# Sheet2.net
KiCad netlist of a schematic drawn in Altium Designer
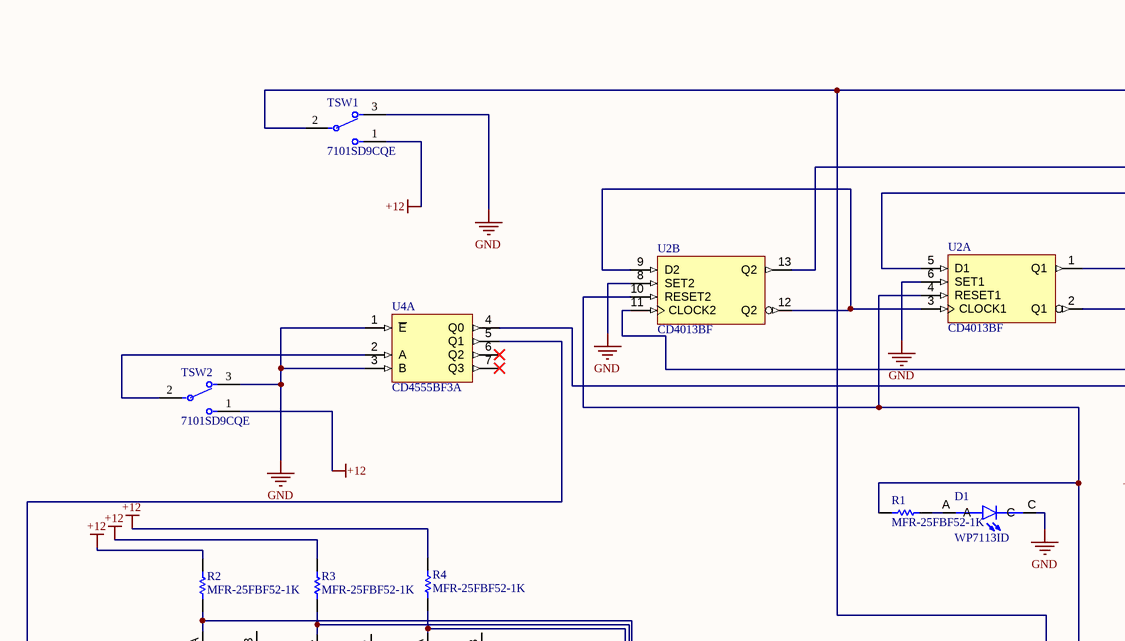
[diagram p0: Sheet2.SchDoc, centre column 2 of 4]
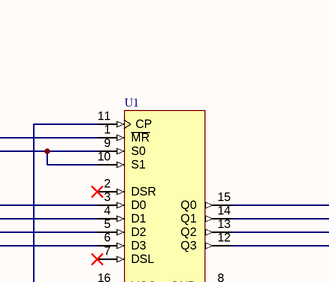
[diagram p1: Sheet2.SchDoc, centre column 3 of 4]
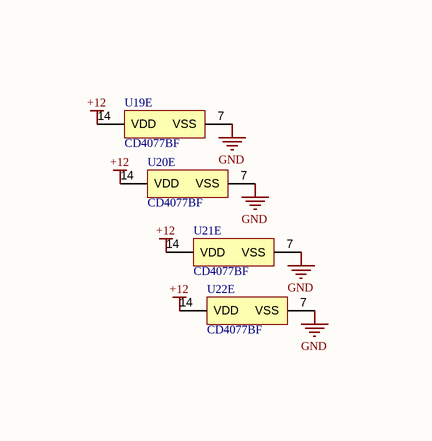
[diagram p2: Sheet2.SchDoc, centre column 4 of 4]
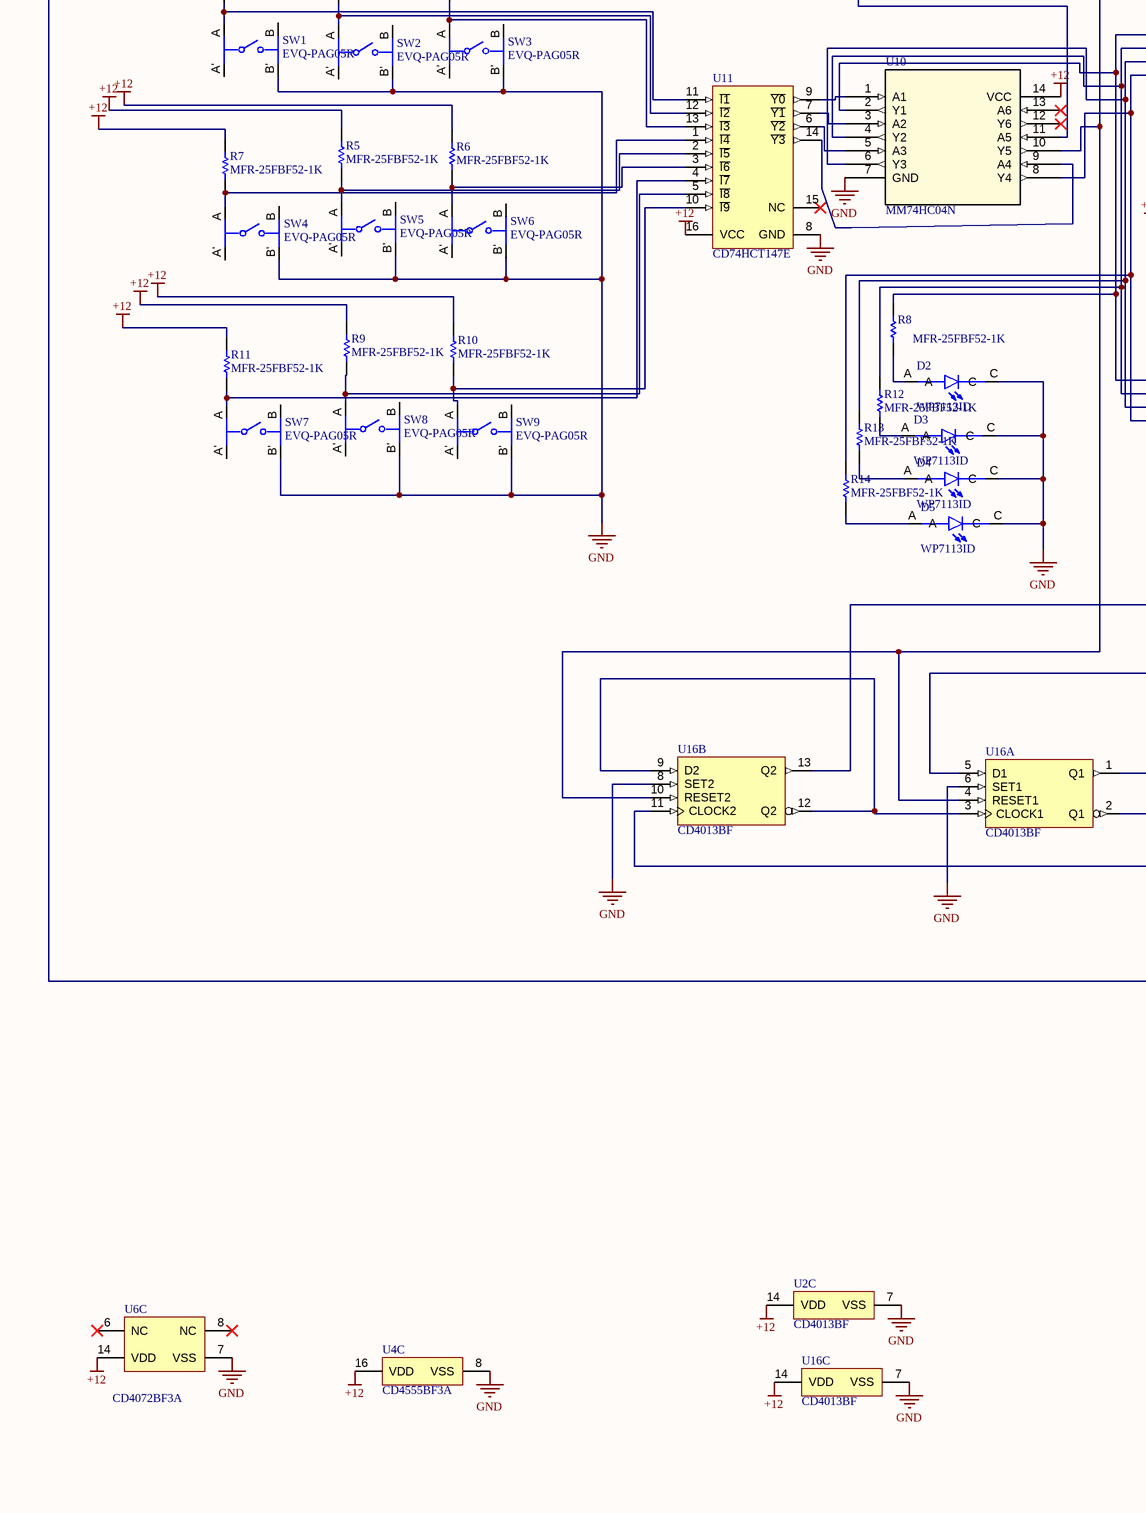
[diagram p3: Sheet2.SchDoc, bottom column 2 of 4]
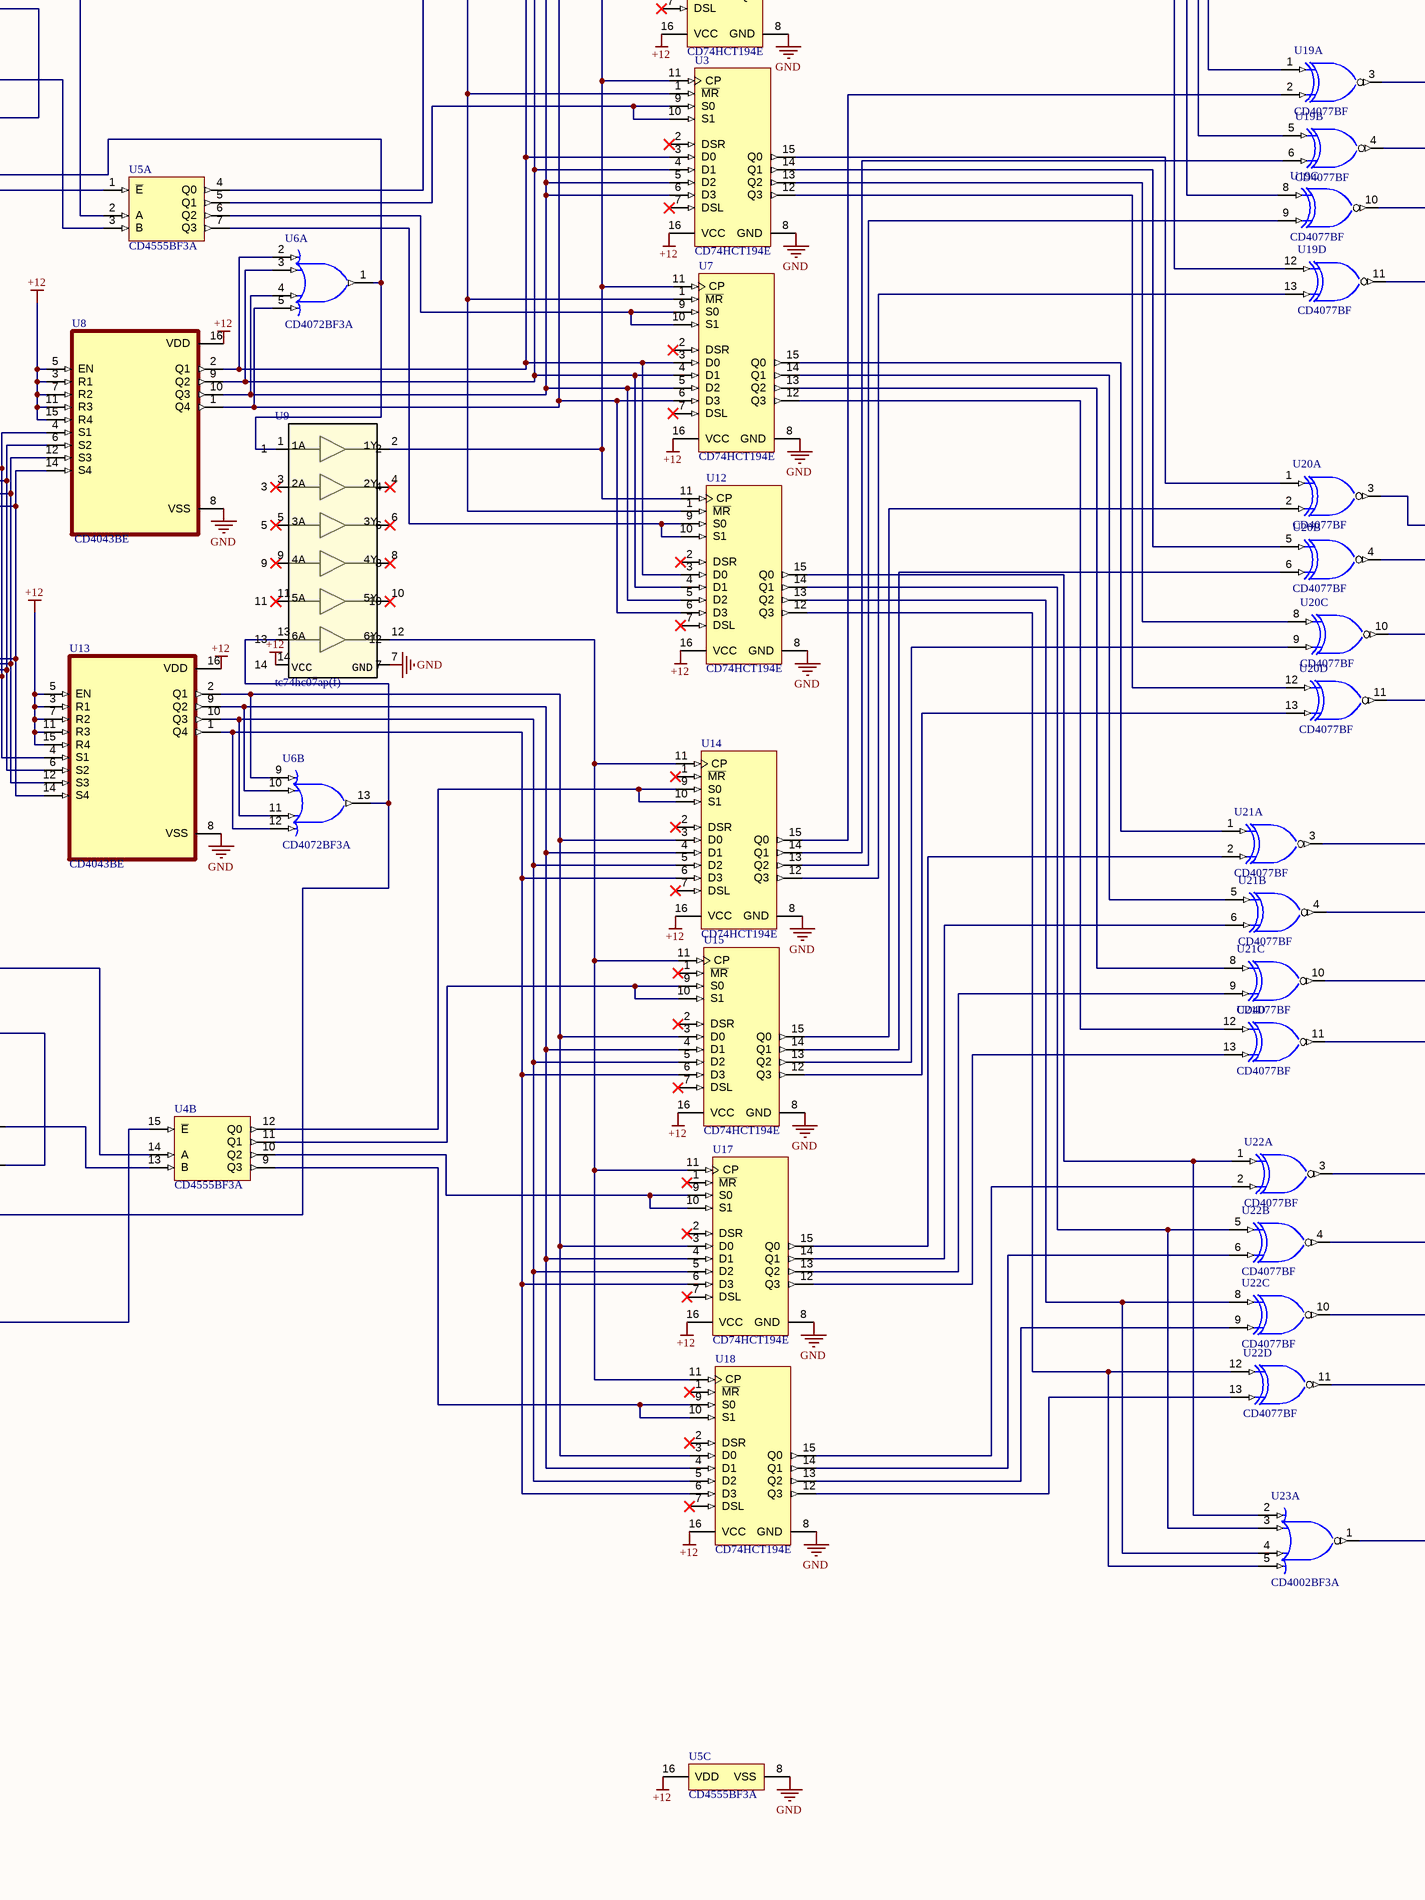
[diagram p4: Sheet2.SchDoc, bottom column 3 of 4]
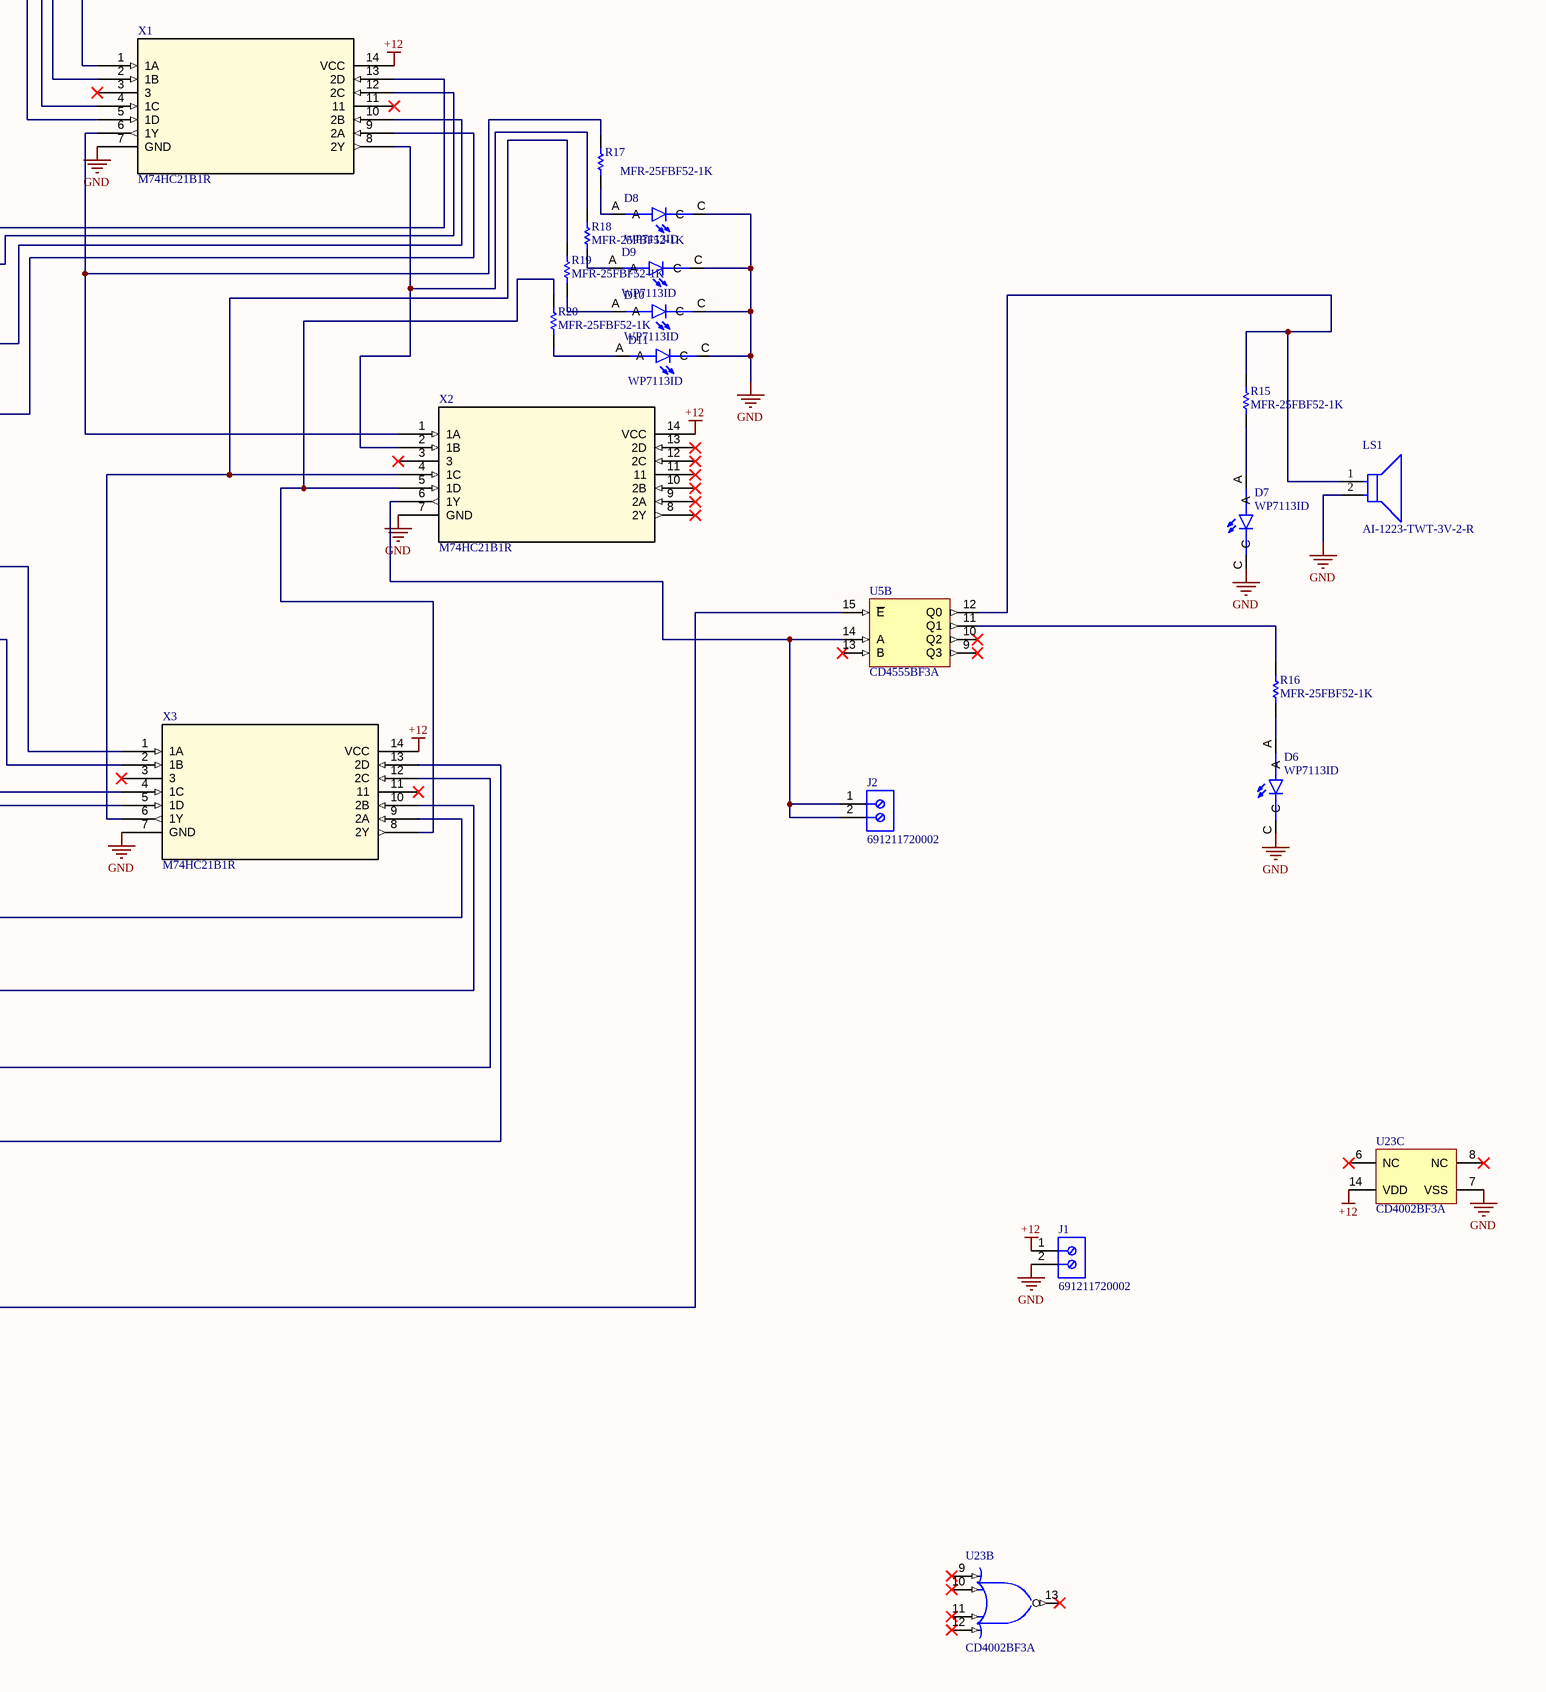
[diagram p5: Sheet2.SchDoc, bottom column 4 of 4]

(export (version "E")
  (design (tool "Eeschema 10.0.6"))
  (components
    (comp (ref "D1")
      (value "WP7113ID")
      (footprint "LED_WP7113ID")
      (description "Red 617nm LED Indication - Discrete 2V Radial")
      (fields (field (name "MF") "Kingbright"))
      (libsource (lib "WP7113ID (1)") (part "WP7113ID"))
    )
    (comp (ref "D2")
      (value "WP7113ID")
      (footprint "LED_WP7113ID")
      (description "Red 617nm LED Indication - Discrete 2V Radial")
      (fields (field (name "MF") "Kingbright"))
      (libsource (lib "WP7113ID") (part "WP7113ID"))
    )
    (comp (ref "D3")
      (value "WP7113ID")
      (footprint "LED_WP7113ID")
      (description "Red 617nm LED Indication - Discrete 2V Radial")
      (fields (field (name "MF") "Kingbright"))
      (libsource (lib "WP7113ID") (part "WP7113ID"))
    )
    (comp (ref "D4")
      (value "WP7113ID")
      (footprint "LED_WP7113ID")
      (description "Red 617nm LED Indication - Discrete 2V Radial")
      (fields (field (name "MF") "Kingbright"))
      (libsource (lib "WP7113ID") (part "WP7113ID"))
    )
    (comp (ref "D5")
      (value "WP7113ID")
      (footprint "LED_WP7113ID")
      (description "Red 617nm LED Indication - Discrete 2V Radial")
      (fields (field (name "MF") "Kingbright"))
      (libsource (lib "WP7113ID") (part "WP7113ID"))
    )
    (comp (ref "D6")
      (value "WP7113ID")
      (footprint "LED_WP7113ID")
      (description "Red 617nm LED Indication - Discrete 2V Radial")
      (fields (field (name "MF") "Kingbright"))
      (libsource (lib "WP7113ID (1)") (part "WP7113ID"))
    )
    (comp (ref "D7")
      (value "WP7113ID")
      (footprint "LED_WP7113ID")
      (description "Red 617nm LED Indication - Discrete 2V Radial")
      (fields (field (name "MF") "Kingbright"))
      (libsource (lib "WP7113ID (1)") (part "WP7113ID"))
    )
    (comp (ref "D8")
      (value "WP7113ID")
      (footprint "LED_WP7113ID")
      (description "Red 617nm LED Indication - Discrete 2V Radial")
      (fields (field (name "MF") "Kingbright"))
      (libsource (lib "WP7113ID") (part "WP7113ID"))
    )
    (comp (ref "D9")
      (value "WP7113ID")
      (footprint "LED_WP7113ID")
      (description "Red 617nm LED Indication - Discrete 2V Radial")
      (fields (field (name "MF") "Kingbright"))
      (libsource (lib "WP7113ID") (part "WP7113ID"))
    )
    (comp (ref "D10")
      (value "WP7113ID")
      (footprint "LED_WP7113ID")
      (description "Red 617nm LED Indication - Discrete 2V Radial")
      (fields (field (name "MF") "Kingbright"))
      (libsource (lib "WP7113ID") (part "WP7113ID"))
    )
    (comp (ref "D11")
      (value "WP7113ID")
      (footprint "LED_WP7113ID")
      (description "Red 617nm LED Indication - Discrete 2V Radial")
      (fields (field (name "MF") "Kingbright"))
      (libsource (lib "WP7113ID") (part "WP7113ID"))
    )
    (comp (ref "J1")
      (value "691211720002")
      (footprint "691211720002")
      (description "211 Series 5MM Pitch Straight, Pcb Terminal Block, Through Hole, 2 Way")
      (fields (field (name "VOLTAGE") "300V"))
      (libsource (lib "Altium Content Vault") (part "TBL - 1R - 02P - Screw"))
    )
    (comp (ref "J2")
      (value "691211720002")
      (footprint "691211720002")
      (description "211 Series 5MM Pitch Straight, Pcb Terminal Block, Through Hole, 2 Way")
      (fields (field (name "VOLTAGE") "300V"))
      (libsource (lib "Altium Content Vault") (part "TBL - 1R - 02P - Screw"))
    )
    (comp (ref "LS1")
      (value "AI-1223-TWT-3V-2-R")
      (footprint "FP-AI-1223-TWT-3V-2-R-MFG")
      (description "BUZZER MAGNETIC 3V 12MM TH")
      (libsource (lib "Altium Content Vault") (part "1973c4b650225fd2ddacaff6b763965"))
    )
    (comp (ref "R1")
      (value "MFR-25FBF52-1K")
      (footprint "RESA60-630X240")
      (description "Axial Resistor, 1 KOhm, +/- 1%, 250 mW, -55 to 155 degC, 2-Pin THD, RoHS, Bulk")
      (fields (field (name "TOLERANCE") "1%"))
      (libsource (lib "Altium Content Vault") (part "RES-2"))
    )
    (comp (ref "R2")
      (value "MFR-25FBF52-1K")
      (footprint "RESA60-630X240")
      (description "Axial Resistor, 1 KOhm, +/- 1%, 250 mW, -55 to 155 degC, 2-Pin THD, RoHS, Bulk")
      (fields (field (name "TOLERANCE") "1%"))
      (libsource (lib "Altium Content Vault") (part "RES-2"))
    )
    (comp (ref "R3")
      (value "MFR-25FBF52-1K")
      (footprint "RESA60-630X240")
      (description "Axial Resistor, 1 KOhm, +/- 1%, 250 mW, -55 to 155 degC, 2-Pin THD, RoHS, Bulk")
      (fields (field (name "TOLERANCE") "1%"))
      (libsource (lib "Altium Content Vault") (part "RES-2"))
    )
    (comp (ref "R4")
      (value "MFR-25FBF52-1K")
      (footprint "RESA60-630X240")
      (description "Axial Resistor, 1 KOhm, +/- 1%, 250 mW, -55 to 155 degC, 2-Pin THD, RoHS, Bulk")
      (fields (field (name "TOLERANCE") "1%"))
      (libsource (lib "Altium Content Vault") (part "RES-2"))
    )
    (comp (ref "R5")
      (value "MFR-25FBF52-1K")
      (footprint "RESA60-630X240")
      (description "Axial Resistor, 1 KOhm, +/- 1%, 250 mW, -55 to 155 degC, 2-Pin THD, RoHS, Bulk")
      (fields (field (name "TOLERANCE") "1%"))
      (libsource (lib "Altium Content Vault") (part "RES-2"))
    )
    (comp (ref "R6")
      (value "MFR-25FBF52-1K")
      (footprint "RESA60-630X240")
      (description "Axial Resistor, 1 KOhm, +/- 1%, 250 mW, -55 to 155 degC, 2-Pin THD, RoHS, Bulk")
      (fields (field (name "TOLERANCE") "1%"))
      (libsource (lib "Altium Content Vault") (part "RES-2"))
    )
    (comp (ref "R7")
      (value "MFR-25FBF52-1K")
      (footprint "RESA60-630X240")
      (description "Axial Resistor, 1 KOhm, +/- 1%, 250 mW, -55 to 155 degC, 2-Pin THD, RoHS, Bulk")
      (fields (field (name "TOLERANCE") "1%"))
      (libsource (lib "Altium Content Vault") (part "RES-2"))
    )
    (comp (ref "R8")
      (value "MFR-25FBF52-1K")
      (footprint "RESA60-630X240")
      (description "Axial Resistor, 1 KOhm, +/- 1%, 250 mW, -55 to 155 degC, 2-Pin THD, RoHS, Bulk")
      (fields (field (name "TOLERANCE") "1%"))
      (libsource (lib "Altium Content Vault") (part "RES-2"))
    )
    (comp (ref "R9")
      (value "MFR-25FBF52-1K")
      (footprint "RESA60-630X240")
      (description "Axial Resistor, 1 KOhm, +/- 1%, 250 mW, -55 to 155 degC, 2-Pin THD, RoHS, Bulk")
      (fields (field (name "TOLERANCE") "1%"))
      (libsource (lib "Altium Content Vault") (part "RES-2"))
    )
    (comp (ref "R10")
      (value "MFR-25FBF52-1K")
      (footprint "RESA60-630X240")
      (description "Axial Resistor, 1 KOhm, +/- 1%, 250 mW, -55 to 155 degC, 2-Pin THD, RoHS, Bulk")
      (fields (field (name "TOLERANCE") "1%"))
      (libsource (lib "Altium Content Vault") (part "RES-2"))
    )
    (comp (ref "R11")
      (value "MFR-25FBF52-1K")
      (footprint "RESA60-630X240")
      (description "Axial Resistor, 1 KOhm, +/- 1%, 250 mW, -55 to 155 degC, 2-Pin THD, RoHS, Bulk")
      (fields (field (name "TOLERANCE") "1%"))
      (libsource (lib "Altium Content Vault") (part "RES-2"))
    )
    (comp (ref "R12")
      (value "MFR-25FBF52-1K")
      (footprint "RESA60-630X240")
      (description "Axial Resistor, 1 KOhm, +/- 1%, 250 mW, -55 to 155 degC, 2-Pin THD, RoHS, Bulk")
      (fields (field (name "TOLERANCE") "1%"))
      (libsource (lib "Altium Content Vault") (part "RES-2"))
    )
    (comp (ref "R13")
      (value "MFR-25FBF52-1K")
      (footprint "RESA60-630X240")
      (description "Axial Resistor, 1 KOhm, +/- 1%, 250 mW, -55 to 155 degC, 2-Pin THD, RoHS, Bulk")
      (fields (field (name "TOLERANCE") "1%"))
      (libsource (lib "Altium Content Vault") (part "RES-2"))
    )
    (comp (ref "R14")
      (value "MFR-25FBF52-1K")
      (footprint "RESA60-630X240")
      (description "Axial Resistor, 1 KOhm, +/- 1%, 250 mW, -55 to 155 degC, 2-Pin THD, RoHS, Bulk")
      (fields (field (name "TOLERANCE") "1%"))
      (libsource (lib "Altium Content Vault") (part "RES-2"))
    )
    (comp (ref "R15")
      (value "MFR-25FBF52-1K")
      (footprint "RESA60-630X240")
      (description "Axial Resistor, 1 KOhm, +/- 1%, 250 mW, -55 to 155 degC, 2-Pin THD, RoHS, Bulk")
      (fields (field (name "TOLERANCE") "1%"))
      (libsource (lib "Altium Content Vault") (part "RES-2"))
    )
    (comp (ref "R16")
      (value "MFR-25FBF52-1K")
      (footprint "RESA60-630X240")
      (description "Axial Resistor, 1 KOhm, +/- 1%, 250 mW, -55 to 155 degC, 2-Pin THD, RoHS, Bulk")
      (fields (field (name "TOLERANCE") "1%"))
      (libsource (lib "Altium Content Vault") (part "RES-2"))
    )
    (comp (ref "R17")
      (value "MFR-25FBF52-1K")
      (footprint "RESA60-630X240")
      (description "Axial Resistor, 1 KOhm, +/- 1%, 250 mW, -55 to 155 degC, 2-Pin THD, RoHS, Bulk")
      (fields (field (name "TOLERANCE") "1%"))
      (libsource (lib "Altium Content Vault") (part "RES-2"))
    )
    (comp (ref "R18")
      (value "MFR-25FBF52-1K")
      (footprint "RESA60-630X240")
      (description "Axial Resistor, 1 KOhm, +/- 1%, 250 mW, -55 to 155 degC, 2-Pin THD, RoHS, Bulk")
      (fields (field (name "TOLERANCE") "1%"))
      (libsource (lib "Altium Content Vault") (part "RES-2"))
    )
    (comp (ref "R19")
      (value "MFR-25FBF52-1K")
      (footprint "RESA60-630X240")
      (description "Axial Resistor, 1 KOhm, +/- 1%, 250 mW, -55 to 155 degC, 2-Pin THD, RoHS, Bulk")
      (fields (field (name "TOLERANCE") "1%"))
      (libsource (lib "Altium Content Vault") (part "RES-2"))
    )
    (comp (ref "R20")
      (value "MFR-25FBF52-1K")
      (footprint "RESA60-630X240")
      (description "Axial Resistor, 1 KOhm, +/- 1%, 250 mW, -55 to 155 degC, 2-Pin THD, RoHS, Bulk")
      (fields (field (name "TOLERANCE") "1%"))
      (libsource (lib "Altium Content Vault") (part "RES-2"))
    )
    (comp (ref "SW1")
      (value "EVQ-PAG05R")
      (footprint "FP-EVQ-PAG05R-MFG")
      (description "SWITCH TACTILE SPST-NO 0.02A 15V")
      (libsource (lib "Altium Content Vault") (part "841f23923f71b23f3ea0ab5dfb78dcc"))
    )
    (comp (ref "SW2")
      (value "EVQ-PAG05R")
      (footprint "FP-EVQ-PAG05R-MFG")
      (description "SWITCH TACTILE SPST-NO 0.02A 15V")
      (libsource (lib "Altium Content Vault") (part "841f23923f71b23f3ea0ab5dfb78dcc"))
    )
    (comp (ref "SW3")
      (value "EVQ-PAG05R")
      (footprint "FP-EVQ-PAG05R-MFG")
      (description "SWITCH TACTILE SPST-NO 0.02A 15V")
      (libsource (lib "Altium Content Vault") (part "841f23923f71b23f3ea0ab5dfb78dcc"))
    )
    (comp (ref "SW4")
      (value "EVQ-PAG05R")
      (footprint "FP-EVQ-PAG05R-MFG")
      (description "SWITCH TACTILE SPST-NO 0.02A 15V")
      (libsource (lib "Altium Content Vault") (part "841f23923f71b23f3ea0ab5dfb78dcc"))
    )
    (comp (ref "SW5")
      (value "EVQ-PAG05R")
      (footprint "FP-EVQ-PAG05R-MFG")
      (description "SWITCH TACTILE SPST-NO 0.02A 15V")
      (libsource (lib "Altium Content Vault") (part "841f23923f71b23f3ea0ab5dfb78dcc"))
    )
    (comp (ref "SW6")
      (value "EVQ-PAG05R")
      (footprint "FP-EVQ-PAG05R-MFG")
      (description "SWITCH TACTILE SPST-NO 0.02A 15V")
      (libsource (lib "Altium Content Vault") (part "841f23923f71b23f3ea0ab5dfb78dcc"))
    )
    (comp (ref "SW7")
      (value "EVQ-PAG05R")
      (footprint "FP-EVQ-PAG05R-MFG")
      (description "SWITCH TACTILE SPST-NO 0.02A 15V")
      (libsource (lib "Altium Content Vault") (part "841f23923f71b23f3ea0ab5dfb78dcc"))
    )
    (comp (ref "SW8")
      (value "EVQ-PAG05R")
      (footprint "FP-EVQ-PAG05R-MFG")
      (description "SWITCH TACTILE SPST-NO 0.02A 15V")
      (libsource (lib "Altium Content Vault") (part "841f23923f71b23f3ea0ab5dfb78dcc"))
    )
    (comp (ref "SW9")
      (value "EVQ-PAG05R")
      (footprint "FP-EVQ-PAG05R-MFG")
      (description "SWITCH TACTILE SPST-NO 0.02A 15V")
      (libsource (lib "Altium Content Vault") (part "841f23923f71b23f3ea0ab5dfb78dcc"))
    )
    (comp (ref "TSW1")
      (value "7101SD9CQE")
      (footprint "FP-7101SD9CQE-MFG")
      (libsource (lib "Altium Content Vault") (part "27fba41b97997be56c5a5b5d23f1c5a"))
    )
    (comp (ref "TSW2")
      (value "7101SD9CQE")
      (footprint "FP-7101SD9CQE-MFG")
      (libsource (lib "Altium Content Vault") (part "27fba41b97997be56c5a5b5d23f1c5a"))
    )
    (comp (ref "U1")
      (value "CD74HCT194E")
      (footprint "N0016A")
      (description "High Speed CMOS Logic 4-Bit Bidirectional Universal Shift Register, N0016A, TUBE")
      (fields
        (field (name "GENERIC PART NUMBER") "CD74HCT194")
        (field (name "MANUFACTURER") "Texas Instruments")
      )
      (libsource (lib "Altium Content Vault") (part "TI-CD74HCX194-16"))
    )
    (comp (ref "U2")
      (value "CD4013BF")
      (footprint "J0014A")
      (description "CMOS Dual D-Type Flip Flop, J0014A, TUBE")
      (fields
        (field (name "GENERIC PART NUMBER") "CD4013B-MIL")
        (field (name "MANUFACTURER") "Texas Instruments")
      )
      (libsource (lib "Altium Content Vault") (part "TI-CD4013B-14"))
    )
    (comp (ref "U3")
      (value "CD74HCT194E")
      (footprint "N0016A")
      (description "High Speed CMOS Logic 4-Bit Bidirectional Universal Shift Register, N0016A, TUBE")
      (fields
        (field (name "GENERIC PART NUMBER") "CD74HCT194")
        (field (name "MANUFACTURER") "Texas Instruments")
      )
      (libsource (lib "Altium Content Vault") (part "TI-CD74HCX194-16"))
    )
    (comp (ref "U4")
      (value "CD4555BF3A")
      (footprint "J0016A")
      (description "CMOS Dual Binary to 1-of-4 Decoder/Demultiplexer with Outputs High on Select, J0016A, TUBE")
      (fields
        (field (name "MANUFACTURER") "Texas Instruments")
        (field (name "GENERIC PART NUMBER") "CD4555B-MIL")
      )
      (libsource (lib "Altium Content Vault") (part "TI-CD4555B-16"))
    )
    (comp (ref "U5")
      (value "CD4555BF3A")
      (footprint "J0016A")
      (description "CMOS Dual Binary to 1-of-4 Decoder/Demultiplexer with Outputs High on Select, J0016A, TUBE")
      (fields
        (field (name "MANUFACTURER") "Texas Instruments")
        (field (name "GENERIC PART NUMBER") "CD4555B-MIL")
      )
      (libsource (lib "Altium Content Vault") (part "TI-CD4555B-16"))
    )
    (comp (ref "U6")
      (value "CD4072BF3A")
      (footprint "J0014A")
      (description "CMOS Dual 4-Input OR Gate, J0014A, TUBE")
      (fields
        (field (name "GENERIC PART NUMBER") "CD4072B-MIL")
        (field (name "MANUFACTURER") "Texas Instruments")
      )
      (libsource (lib "Altium Content Vault") (part "TI-CD4072B-14"))
    )
    (comp (ref "U7")
      (value "CD74HCT194E")
      (footprint "N0016A")
      (description "High Speed CMOS Logic 4-Bit Bidirectional Universal Shift Register, N0016A, TUBE")
      (fields
        (field (name "GENERIC PART NUMBER") "CD74HCT194")
        (field (name "MANUFACTURER") "Texas Instruments")
      )
      (libsource (lib "Altium Content Vault") (part "TI-CD74HCX194-16"))
    )
    (comp (ref "U8")
      (value "CD4043BE")
      (footprint "DIP794W45P254L1969H508Q16")
      (description "CMOS Quad NOR R/S Latch with 3-State Outputs")
      (fields (field (name "MF") "Texas Instruments"))
      (libsource (lib "CD4043BE") (part "CD4043BE"))
    )
    (comp (ref "U9")
      (value "tc74hc07ap(f)")
      (footprint "DIP14_TOS")
      (description "Hex Buffer, DIP14")
      (fields (field (name "COPYRIGHT") "Copyright (C) 2025 Ultra Librarian. All rights reserved."))
      (libsource (lib "tc74hc07apf") (part "tc74hc07apf"))
    )
    (comp (ref "U10")
      (value "MM74HC04N")
      (footprint "PDIP14_19P56X6P35_ONS")
      (description "Description")
      (fields (field (name "COPYRIGHT") "Copyright (C) 2026 Ultra Librarian. All rights reserved."))
      (libsource (lib "MM74HC04N") (part "MM74HC04N"))
    )
    (comp (ref "U11")
      (value "CD74HCT147E")
      (footprint "N0016A")
      (description "High Speed CMOS Logic 10-to-4 Line Priority Encoder, N0016A, TUBE")
      (fields
        (field (name "MANUFACTURER") "Texas Instruments")
        (field (name "GENERIC PART NUMBER") "CD74HCT147")
      )
      (libsource (lib "Altium Content Vault") (part "TI-CDX4HCX147-16"))
    )
    (comp (ref "U12")
      (value "CD74HCT194E")
      (footprint "N0016A")
      (description "High Speed CMOS Logic 4-Bit Bidirectional Universal Shift Register, N0016A, TUBE")
      (fields
        (field (name "GENERIC PART NUMBER") "CD74HCT194")
        (field (name "MANUFACTURER") "Texas Instruments")
      )
      (libsource (lib "Altium Content Vault") (part "TI-CD74HCX194-16"))
    )
    (comp (ref "U13")
      (value "CD4043BE")
      (footprint "DIP794W45P254L1969H508Q16")
      (description "CMOS Quad NOR R/S Latch with 3-State Outputs")
      (fields (field (name "MF") "Texas Instruments"))
      (libsource (lib "CD4043BE") (part "CD4043BE"))
    )
    (comp (ref "U14")
      (value "CD74HCT194E")
      (footprint "N0016A")
      (description "High Speed CMOS Logic 4-Bit Bidirectional Universal Shift Register, N0016A, TUBE")
      (fields
        (field (name "GENERIC PART NUMBER") "CD74HCT194")
        (field (name "MANUFACTURER") "Texas Instruments")
      )
      (libsource (lib "Altium Content Vault") (part "TI-CD74HCX194-16"))
    )
    (comp (ref "U15")
      (value "CD74HCT194E")
      (footprint "N0016A")
      (description "High Speed CMOS Logic 4-Bit Bidirectional Universal Shift Register, N0016A, TUBE")
      (fields
        (field (name "GENERIC PART NUMBER") "CD74HCT194")
        (field (name "MANUFACTURER") "Texas Instruments")
      )
      (libsource (lib "Altium Content Vault") (part "TI-CD74HCX194-16"))
    )
    (comp (ref "U16")
      (value "CD4013BF")
      (footprint "J0014A")
      (description "CMOS Dual D-Type Flip Flop, J0014A, TUBE")
      (fields
        (field (name "GENERIC PART NUMBER") "CD4013B-MIL")
        (field (name "MANUFACTURER") "Texas Instruments")
      )
      (libsource (lib "Altium Content Vault") (part "TI-CD4013B-14"))
    )
    (comp (ref "U17")
      (value "CD74HCT194E")
      (footprint "N0016A")
      (description "High Speed CMOS Logic 4-Bit Bidirectional Universal Shift Register, N0016A, TUBE")
      (fields
        (field (name "GENERIC PART NUMBER") "CD74HCT194")
        (field (name "MANUFACTURER") "Texas Instruments")
      )
      (libsource (lib "Altium Content Vault") (part "TI-CD74HCX194-16"))
    )
    (comp (ref "U18")
      (value "CD74HCT194E")
      (footprint "N0016A")
      (description "High Speed CMOS Logic 4-Bit Bidirectional Universal Shift Register, N0016A, TUBE")
      (fields
        (field (name "GENERIC PART NUMBER") "CD74HCT194")
        (field (name "MANUFACTURER") "Texas Instruments")
      )
      (libsource (lib "Altium Content Vault") (part "TI-CD74HCX194-16"))
    )
    (comp (ref "U19")
      (value "CD4077BF")
      (footprint "J0014A")
      (description "CMOS Quad Exclusive-NOR Gate, J0014A, TUBE")
      (fields
        (field (name "MANUFACTURER") "Texas Instruments")
        (field (name "GENERIC PART NUMBER") "CD4077B-MIL")
      )
      (libsource (lib "Altium Content Vault") (part "TI-XNOR-4-2IN-14"))
    )
    (comp (ref "U20")
      (value "CD4077BF")
      (footprint "J0014A")
      (description "CMOS Quad Exclusive-NOR Gate, J0014A, TUBE")
      (fields
        (field (name "MANUFACTURER") "Texas Instruments")
        (field (name "GENERIC PART NUMBER") "CD4077B-MIL")
      )
      (libsource (lib "Altium Content Vault") (part "TI-XNOR-4-2IN-14"))
    )
    (comp (ref "U21")
      (value "CD4077BF")
      (footprint "J0014A")
      (description "CMOS Quad Exclusive-NOR Gate, J0014A, TUBE")
      (fields
        (field (name "MANUFACTURER") "Texas Instruments")
        (field (name "GENERIC PART NUMBER") "CD4077B-MIL")
      )
      (libsource (lib "Altium Content Vault") (part "TI-XNOR-4-2IN-14"))
    )
    (comp (ref "U22")
      (value "CD4077BF")
      (footprint "J0014A")
      (description "CMOS Quad Exclusive-NOR Gate, J0014A, TUBE")
      (fields
        (field (name "MANUFACTURER") "Texas Instruments")
        (field (name "GENERIC PART NUMBER") "CD4077B-MIL")
      )
      (libsource (lib "Altium Content Vault") (part "TI-XNOR-4-2IN-14"))
    )
    (comp (ref "U23")
      (value "CD4002BF3A")
      (footprint "J0014A")
      (description "CMOS Dual 4-Input NOR Gate, J0014A, TUBE")
      (fields
        (field (name "MANUFACTURER") "Texas Instruments")
        (field (name "GENERIC PART NUMBER") "CD4002B-MIL")
      )
      (libsource (lib "Altium Content Vault") (part "TI-CD4002B-MIL-J0014A-14"))
    )
    (comp (ref "X1")
      (value "M74HC21B1R")
      (footprint "DIP14_300_STH")
      (description "No Description Available")
      (fields (field (name "COPYRIGHT") "Copyright (C) 2026 Ultra Librarian. All rights reserved."))
      (libsource (lib "M74HC21B1R") (part "M74HC21B1R"))
    )
    (comp (ref "X2")
      (value "M74HC21B1R")
      (footprint "DIP14_300_STH")
      (description "No Description Available")
      (fields (field (name "COPYRIGHT") "Copyright (C) 2026 Ultra Librarian. All rights reserved."))
      (libsource (lib "M74HC21B1R") (part "M74HC21B1R"))
    )
    (comp (ref "X3")
      (value "M74HC21B1R")
      (footprint "DIP14_300_STH")
      (description "No Description Available")
      (fields (field (name "COPYRIGHT") "Copyright (C) 2026 Ultra Librarian. All rights reserved."))
      (libsource (lib "M74HC21B1R") (part "M74HC21B1R"))
    )
  )
  (nets
    (net (code "1") (name "+12") (class "Default")
      (node (ref "J1") (pin "1") (pinfunction "1_1") (pintype "passive"))
      (node (ref "R10") (pin "2") (pinfunction "2_2") (pintype "passive"))
      (node (ref "R11") (pin "2") (pinfunction "2_2") (pintype "passive"))
      (node (ref "R2") (pin "2") (pinfunction "2_2") (pintype "passive"))
      (node (ref "R3") (pin "2") (pinfunction "2_2") (pintype "passive"))
      (node (ref "R4") (pin "2") (pinfunction "2_2") (pintype "passive"))
      (node (ref "R5") (pin "2") (pinfunction "2_2") (pintype "passive"))
      (node (ref "R6") (pin "2") (pinfunction "2_2") (pintype "passive"))
      (node (ref "R7") (pin "2") (pinfunction "2_2") (pintype "passive"))
      (node (ref "R9") (pin "2") (pinfunction "2_2") (pintype "passive"))
      (node (ref "TSW1") (pin "1") (pinfunction "1_1") (pintype "passive"))
      (node (ref "TSW2") (pin "1") (pinfunction "1_1") (pintype "passive"))
      (node (ref "U1") (pin "16") (pinfunction "VCC_16") (pintype "power_in"))
      (node (ref "U10") (pin "14") (pinfunction "VCC_14") (pintype "power_in"))
      (node (ref "U11") (pin "16") (pinfunction "VCC_16") (pintype "power_in"))
      (node (ref "U12") (pin "16") (pinfunction "VCC_16") (pintype "power_in"))
      (node (ref "U13") (pin "11") (pinfunction "R3_11") (pintype "input"))
      (node (ref "U13") (pin "15") (pinfunction "R4_15") (pintype "input"))
      (node (ref "U13") (pin "16") (pinfunction "VDD_16") (pintype "power_in"))
      (node (ref "U13") (pin "3") (pinfunction "R1_3") (pintype "input"))
      (node (ref "U13") (pin "5") (pinfunction "EN_5") (pintype "input"))
      (node (ref "U13") (pin "7") (pinfunction "R2_7") (pintype "input"))
      (node (ref "U14") (pin "16") (pinfunction "VCC_16") (pintype "power_in"))
      (node (ref "U15") (pin "16") (pinfunction "VCC_16") (pintype "power_in"))
      (node (ref "U16") (pin "14") (pinfunction "VDD_14") (pintype "power_in"))
      (node (ref "U17") (pin "16") (pinfunction "VCC_16") (pintype "power_in"))
      (node (ref "U18") (pin "16") (pinfunction "VCC_16") (pintype "power_in"))
      (node (ref "U19") (pin "14") (pinfunction "VDD_14") (pintype "power_in"))
      (node (ref "U2") (pin "14") (pinfunction "VDD_14") (pintype "power_in"))
      (node (ref "U20") (pin "14") (pinfunction "VDD_14") (pintype "power_in"))
      (node (ref "U21") (pin "14") (pinfunction "VDD_14") (pintype "power_in"))
      (node (ref "U22") (pin "14") (pinfunction "VDD_14") (pintype "power_in"))
      (node (ref "U23") (pin "14") (pinfunction "VDD_14") (pintype "power_in"))
      (node (ref "U3") (pin "16") (pinfunction "VCC_16") (pintype "power_in"))
      (node (ref "U4") (pin "16") (pinfunction "VDD_16") (pintype "power_in"))
      (node (ref "U5") (pin "16") (pinfunction "VDD_16") (pintype "power_in"))
      (node (ref "U6") (pin "14") (pinfunction "VDD_14") (pintype "power_in"))
      (node (ref "U7") (pin "16") (pinfunction "VCC_16") (pintype "power_in"))
      (node (ref "U8") (pin "11") (pinfunction "R3_11") (pintype "input"))
      (node (ref "U8") (pin "15") (pinfunction "R4_15") (pintype "input"))
      (node (ref "U8") (pin "16") (pinfunction "VDD_16") (pintype "power_in"))
      (node (ref "U8") (pin "3") (pinfunction "R1_3") (pintype "input"))
      (node (ref "U8") (pin "5") (pinfunction "EN_5") (pintype "input"))
      (node (ref "U8") (pin "7") (pinfunction "R2_7") (pintype "input"))
      (node (ref "U9") (pin "14") (pinfunction "14_14") (pintype "passive"))
      (node (ref "X1") (pin "14") (pinfunction "VCC_14") (pintype "power_in"))
      (node (ref "X2") (pin "14") (pinfunction "VCC_14") (pintype "power_in"))
      (node (ref "X3") (pin "14") (pinfunction "VCC_14") (pintype "power_in"))
    )
    (net (code "2") (name "GND") (class "Default")
      (node (ref "D1") (pin "C") (pinfunction "C_C") (pintype "passive"))
      (node (ref "D10") (pin "C") (pinfunction "C_C") (pintype "passive"))
      (node (ref "D11") (pin "C") (pinfunction "C_C") (pintype "passive"))
      (node (ref "D2") (pin "C") (pinfunction "C_C") (pintype "passive"))
      (node (ref "D3") (pin "C") (pinfunction "C_C") (pintype "passive"))
      (node (ref "D4") (pin "C") (pinfunction "C_C") (pintype "passive"))
      (node (ref "D5") (pin "C") (pinfunction "C_C") (pintype "passive"))
      (node (ref "D6") (pin "C") (pinfunction "C_C") (pintype "passive"))
      (node (ref "D7") (pin "C") (pinfunction "C_C") (pintype "passive"))
      (node (ref "D8") (pin "C") (pinfunction "C_C") (pintype "passive"))
      (node (ref "D9") (pin "C") (pinfunction "C_C") (pintype "passive"))
      (node (ref "J1") (pin "2") (pinfunction "2_2") (pintype "passive"))
      (node (ref "LS1") (pin "2") (pinfunction "A_2") (pintype "passive"))
      (node (ref "SW1") (pin "B'") (pinfunction "B'_B'") (pintype "passive"))
      (node (ref "SW2") (pin "B'") (pinfunction "B'_B'") (pintype "passive"))
      (node (ref "SW3") (pin "B'") (pinfunction "B'_B'") (pintype "passive"))
      (node (ref "SW4") (pin "B'") (pinfunction "B'_B'") (pintype "passive"))
      (node (ref "SW5") (pin "B'") (pinfunction "B'_B'") (pintype "passive"))
      (node (ref "SW6") (pin "B'") (pinfunction "B'_B'") (pintype "passive"))
      (node (ref "SW7") (pin "B'") (pinfunction "B'_B'") (pintype "passive"))
      (node (ref "SW8") (pin "B'") (pinfunction "B'_B'") (pintype "passive"))
      (node (ref "SW9") (pin "B'") (pinfunction "B'_B'") (pintype "passive"))
      (node (ref "TSW1") (pin "3") (pinfunction "3_3") (pintype "passive"))
      (node (ref "TSW2") (pin "3") (pinfunction "3_3") (pintype "passive"))
      (node (ref "U1") (pin "8") (pinfunction "GND_8") (pintype "power_in"))
      (node (ref "U10") (pin "7") (pinfunction "GND_7") (pintype "power_in"))
      (node (ref "U11") (pin "8") (pinfunction "GND_8") (pintype "power_in"))
      (node (ref "U12") (pin "8") (pinfunction "GND_8") (pintype "power_in"))
      (node (ref "U13") (pin "8") (pinfunction "VSS_8") (pintype "power_in"))
      (node (ref "U14") (pin "8") (pinfunction "GND_8") (pintype "power_in"))
      (node (ref "U15") (pin "8") (pinfunction "GND_8") (pintype "power_in"))
      (node (ref "U16") (pin "6") (pinfunction "SET1_6") (pintype "input"))
      (node (ref "U16") (pin "7") (pinfunction "VSS_7") (pintype "power_in"))
      (node (ref "U16") (pin "8") (pinfunction "SET2_8") (pintype "input"))
      (node (ref "U17") (pin "8") (pinfunction "GND_8") (pintype "power_in"))
      (node (ref "U18") (pin "8") (pinfunction "GND_8") (pintype "power_in"))
      (node (ref "U19") (pin "7") (pinfunction "VSS_7") (pintype "power_in"))
      (node (ref "U2") (pin "6") (pinfunction "SET1_6") (pintype "input"))
      (node (ref "U2") (pin "7") (pinfunction "VSS_7") (pintype "power_in"))
      (node (ref "U2") (pin "8") (pinfunction "SET2_8") (pintype "input"))
      (node (ref "U20") (pin "7") (pinfunction "VSS_7") (pintype "power_in"))
      (node (ref "U21") (pin "7") (pinfunction "VSS_7") (pintype "power_in"))
      (node (ref "U22") (pin "7") (pinfunction "VSS_7") (pintype "power_in"))
      (node (ref "U23") (pin "7") (pinfunction "VSS_7") (pintype "power_in"))
      (node (ref "U3") (pin "8") (pinfunction "GND_8") (pintype "power_in"))
      (node (ref "U4") (pin "1") (pinfunction "~{E}_1") (pintype "input"))
      (node (ref "U4") (pin "3") (pinfunction "B_3") (pintype "input"))
      (node (ref "U4") (pin "8") (pinfunction "VSS_8") (pintype "power_in"))
      (node (ref "U5") (pin "8") (pinfunction "VSS_8") (pintype "power_in"))
      (node (ref "U6") (pin "7") (pinfunction "VSS_7") (pintype "power_in"))
      (node (ref "U7") (pin "8") (pinfunction "GND_8") (pintype "power_in"))
      (node (ref "U8") (pin "8") (pinfunction "VSS_8") (pintype "power_in"))
      (node (ref "U9") (pin "7") (pinfunction "7_7") (pintype "passive"))
      (node (ref "X1") (pin "7") (pinfunction "GND_7") (pintype "power_in"))
      (node (ref "X2") (pin "7") (pinfunction "GND_7") (pintype "power_in"))
      (node (ref "X3") (pin "7") (pinfunction "GND_7") (pintype "power_in"))
    )
    (net (code "3") (name "Net-(D1-PadA)") (class "Default")
      (node (ref "D1") (pin "A") (pinfunction "A_A") (pintype "passive"))
      (node (ref "R1") (pin "2") (pinfunction "2_2") (pintype "passive"))
    )
    (net (code "4") (name "Net-(D2-PadA)") (class "Default")
      (node (ref "D2") (pin "A") (pinfunction "A_A") (pintype "passive"))
      (node (ref "R8") (pin "1") (pinfunction "1_1") (pintype "passive"))
    )
    (net (code "5") (name "Net-(D3-PadA)") (class "Default")
      (node (ref "D3") (pin "A") (pinfunction "A_A") (pintype "passive"))
      (node (ref "R12") (pin "1") (pinfunction "1_1") (pintype "passive"))
    )
    (net (code "6") (name "Net-(D4-PadA)") (class "Default")
      (node (ref "D4") (pin "A") (pinfunction "A_A") (pintype "passive"))
      (node (ref "R13") (pin "1") (pinfunction "1_1") (pintype "passive"))
    )
    (net (code "7") (name "Net-(D5-PadA)") (class "Default")
      (node (ref "D5") (pin "A") (pinfunction "A_A") (pintype "passive"))
      (node (ref "R14") (pin "1") (pinfunction "1_1") (pintype "passive"))
    )
    (net (code "8") (name "Net-(D6-PadA)") (class "Default")
      (node (ref "D6") (pin "A") (pinfunction "A_A") (pintype "passive"))
      (node (ref "R16") (pin "1") (pinfunction "1_1") (pintype "passive"))
    )
    (net (code "9") (name "Net-(D7-PadA)") (class "Default")
      (node (ref "D7") (pin "A") (pinfunction "A_A") (pintype "passive"))
      (node (ref "R15") (pin "1") (pinfunction "1_1") (pintype "passive"))
    )
    (net (code "10") (name "Net-(D8-PadA)") (class "Default")
      (node (ref "D8") (pin "A") (pinfunction "A_A") (pintype "passive"))
      (node (ref "R17") (pin "1") (pinfunction "1_1") (pintype "passive"))
    )
    (net (code "11") (name "Net-(D9-PadA)") (class "Default")
      (node (ref "D9") (pin "A") (pinfunction "A_A") (pintype "passive"))
      (node (ref "R18") (pin "1") (pinfunction "1_1") (pintype "passive"))
    )
    (net (code "12") (name "Net-(D10-PadA)") (class "Default")
      (node (ref "D10") (pin "A") (pinfunction "A_A") (pintype "passive"))
      (node (ref "R19") (pin "1") (pinfunction "1_1") (pintype "passive"))
    )
    (net (code "13") (name "Net-(D11-PadA)") (class "Default")
      (node (ref "D11") (pin "A") (pinfunction "A_A") (pintype "passive"))
      (node (ref "R20") (pin "1") (pinfunction "1_1") (pintype "passive"))
    )
    (net (code "14") (name "Net-(LS1-C)") (class "Default")
      (node (ref "LS1") (pin "1") (pinfunction "C_1") (pintype "passive"))
      (node (ref "R15") (pin "2") (pinfunction "2_2") (pintype "passive"))
      (node (ref "U5") (pin "12") (pinfunction "Q0_12") (pintype "output"))
    )
    (net (code "15") (name "Net-(TSW1-COMM)") (class "Default")
      (node (ref "TSW1") (pin "2") (pinfunction "COMM_2") (pintype "passive"))
      (node (ref "U1") (pin "1") (pinfunction "~{MR}_1") (pintype "input"))
      (node (ref "U10") (pin "11") (pinfunction "A5_11") (pintype "input"))
      (node (ref "U12") (pin "1") (pinfunction "~{MR}_1") (pintype "input"))
      (node (ref "U3") (pin "1") (pinfunction "~{MR}_1") (pintype "input"))
      (node (ref "U7") (pin "1") (pinfunction "~{MR}_1") (pintype "input"))
    )
    (net (code "16") (name "Net-(TSW2-COMM)") (class "Default")
      (node (ref "TSW2") (pin "2") (pinfunction "COMM_2") (pintype "passive"))
      (node (ref "U4") (pin "2") (pinfunction "A_2") (pintype "input"))
    )
    (net (code "17") (name "Net-(U1-CP)") (class "Default")
      (node (ref "U1") (pin "11") (pinfunction "CP_11") (pintype "input"))
      (node (ref "U12") (pin "11") (pinfunction "CP_11") (pintype "input"))
      (node (ref "U3") (pin "11") (pinfunction "CP_11") (pintype "input"))
      (node (ref "U7") (pin "11") (pinfunction "CP_11") (pintype "input"))
      (node (ref "U9") (pin "2") (pinfunction "2_2") (pintype "passive"))
    )
    (net (code "18") (name "Net-(U1-D0)") (class "Default")
      (node (ref "U1") (pin "3") (pinfunction "D0_3") (pintype "input"))
      (node (ref "U12") (pin "3") (pinfunction "D0_3") (pintype "input"))
      (node (ref "U3") (pin "3") (pinfunction "D0_3") (pintype "input"))
      (node (ref "U6") (pin "2") (pinfunction "A_2") (pintype "input"))
      (node (ref "U7") (pin "3") (pinfunction "D0_3") (pintype "input"))
      (node (ref "U8") (pin "2") (pinfunction "Q1_2") (pintype "output"))
    )
    (net (code "19") (name "Net-(U1-D1)") (class "Default")
      (node (ref "U1") (pin "4") (pinfunction "D1_4") (pintype "input"))
      (node (ref "U12") (pin "4") (pinfunction "D1_4") (pintype "input"))
      (node (ref "U3") (pin "4") (pinfunction "D1_4") (pintype "input"))
      (node (ref "U6") (pin "3") (pinfunction "B_3") (pintype "input"))
      (node (ref "U7") (pin "4") (pinfunction "D1_4") (pintype "input"))
      (node (ref "U8") (pin "9") (pinfunction "Q2_9") (pintype "output"))
    )
    (net (code "20") (name "Net-(U1-D2)") (class "Default")
      (node (ref "U1") (pin "5") (pinfunction "D2_5") (pintype "input"))
      (node (ref "U12") (pin "5") (pinfunction "D2_5") (pintype "input"))
      (node (ref "U3") (pin "5") (pinfunction "D2_5") (pintype "input"))
      (node (ref "U3") (pin "6") (pinfunction "D3_6") (pintype "input"))
      (node (ref "U6") (pin "4") (pinfunction "C_4") (pintype "input"))
      (node (ref "U7") (pin "5") (pinfunction "D2_5") (pintype "input"))
      (node (ref "U8") (pin "10") (pinfunction "Q3_10") (pintype "output"))
    )
    (net (code "21") (name "Net-(U1-D3)") (class "Default")
      (node (ref "U1") (pin "6") (pinfunction "D3_6") (pintype "input"))
      (node (ref "U12") (pin "6") (pinfunction "D3_6") (pintype "input"))
      (node (ref "U6") (pin "5") (pinfunction "D_5") (pintype "input"))
      (node (ref "U7") (pin "6") (pinfunction "D3_6") (pintype "input"))
      (node (ref "U8") (pin "1") (pinfunction "Q4_1") (pintype "output"))
    )
    (net (code "22") (name "Net-(U1-Q0)") (class "Default")
      (node (ref "U1") (pin "15") (pinfunction "Q0_15") (pintype "output"))
      (node (ref "U19") (pin "1") (pinfunction "A_1") (pintype "input"))
    )
    (net (code "23") (name "Net-(U1-Q1)") (class "Default")
      (node (ref "U1") (pin "14") (pinfunction "Q1_14") (pintype "output"))
      (node (ref "U19") (pin "5") (pinfunction "C_5") (pintype "input"))
    )
    (net (code "24") (name "Net-(U1-Q2)") (class "Default")
      (node (ref "U1") (pin "13") (pinfunction "Q2_13") (pintype "output"))
      (node (ref "U19") (pin "8") (pinfunction "E_8") (pintype "input"))
    )
    (net (code "25") (name "Net-(U1-Q3)") (class "Default")
      (node (ref "U1") (pin "12") (pinfunction "Q3_12") (pintype "output"))
      (node (ref "U19") (pin "12") (pinfunction "G_12") (pintype "input"))
    )
    (net (code "26") (name "Net-(U1-S0)") (class "Default")
      (node (ref "U1") (pin "10") (pinfunction "S1_10") (pintype "input"))
      (node (ref "U1") (pin "9") (pinfunction "S0_9") (pintype "input"))
      (node (ref "U5") (pin "4") (pinfunction "Q0_4") (pintype "output"))
    )
    (net (code "27") (name "Net-(U2A-CLOCK1)") (class "Default")
      (node (ref "U2") (pin "12") (pinfunction "Q2_12") (pintype "output"))
      (node (ref "U2") (pin "3") (pinfunction "CLOCK1_3") (pintype "input"))
      (node (ref "U2") (pin "9") (pinfunction "D2_9") (pintype "input"))
    )
    (net (code "28") (name "Net-(U2A-D1)") (class "Default")
      (node (ref "U2") (pin "2") (pinfunction "Q1_2") (pintype "output"))
      (node (ref "U2") (pin "5") (pinfunction "D1_5") (pintype "input"))
    )
    (net (code "29") (name "Net-(U2B-CLOCK2)") (class "Default")
      (node (ref "U2") (pin "11") (pinfunction "CLOCK2_11") (pintype "input"))
      (node (ref "U6") (pin "1") (pinfunction "J_1") (pintype "output"))
      (node (ref "U9") (pin "1") (pinfunction "1_1") (pintype "passive"))
    )
    (net (code "30") (name "Net-(U3-S0)") (class "Default")
      (node (ref "U3") (pin "10") (pinfunction "S1_10") (pintype "input"))
      (node (ref "U3") (pin "9") (pinfunction "S0_9") (pintype "input"))
      (node (ref "U5") (pin "5") (pinfunction "Q1_5") (pintype "output"))
    )
    (net (code "31") (name "Net-(U4A-Q0)") (class "Default")
      (node (ref "U4") (pin "4") (pinfunction "Q0_4") (pintype "output"))
      (node (ref "U5") (pin "1") (pinfunction "~{E}_1") (pintype "input"))
    )
    (net (code "32") (name "Net-(U4A-Q1)") (class "Default")
      (node (ref "U4") (pin "15") (pinfunction "~{E}_15") (pintype "input"))
      (node (ref "U4") (pin "5") (pinfunction "Q1_5") (pintype "output"))
    )
    (net (code "33") (name "Net-(U4B-A)") (class "Default")
      (node (ref "U16") (pin "13") (pinfunction "Q2_13") (pintype "output"))
      (node (ref "U4") (pin "14") (pinfunction "A_14") (pintype "input"))
    )
    (net (code "34") (name "Net-(U4B-B)") (class "Default")
      (node (ref "U16") (pin "1") (pinfunction "Q1_1") (pintype "output"))
      (node (ref "U4") (pin "13") (pinfunction "B_13") (pintype "input"))
    )
    (net (code "35") (name "Net-(U5A-A)") (class "Default")
      (node (ref "U2") (pin "13") (pinfunction "Q2_13") (pintype "output"))
      (node (ref "U5") (pin "2") (pinfunction "A_2") (pintype "input"))
    )
    (net (code "36") (name "Net-(U5A-B)") (class "Default")
      (node (ref "U2") (pin "1") (pinfunction "Q1_1") (pintype "output"))
      (node (ref "U5") (pin "3") (pinfunction "B_3") (pintype "input"))
    )
    (net (code "37") (name "Net-(U5A-Q2)") (class "Default")
      (node (ref "U5") (pin "6") (pinfunction "Q2_6") (pintype "output"))
      (node (ref "U7") (pin "10") (pinfunction "S1_10") (pintype "input"))
      (node (ref "U7") (pin "9") (pinfunction "S0_9") (pintype "input"))
    )
    (net (code "38") (name "Net-(U5B-A)") (class "Default")
      (node (ref "J2") (pin "1") (pinfunction "1_1") (pintype "passive"))
      (node (ref "J2") (pin "2") (pinfunction "2_2") (pintype "passive"))
      (node (ref "U5") (pin "14") (pinfunction "A_14") (pintype "input"))
      (node (ref "X2") (pin "6") (pinfunction "1Y_6") (pintype "output"))
    )
    (net (code "39") (name "Net-(U5B-Q1)") (class "Default")
      (node (ref "R16") (pin "2") (pinfunction "2_2") (pintype "passive"))
      (node (ref "U5") (pin "11") (pinfunction "Q1_11") (pintype "output"))
    )
    (net (code "40") (name "Net-(U10-A1)") (class "Default")
      (node (ref "U10") (pin "1") (pinfunction "A1_1") (pintype "input"))
      (node (ref "U11") (pin "9") (pinfunction "~{Y0}_9") (pintype "output"))
    )
    (net (code "41") (name "Net-(U10-A2)") (class "Default")
      (node (ref "U10") (pin "3") (pinfunction "A2_3") (pintype "input"))
      (node (ref "U11") (pin "7") (pinfunction "~{Y1}_7") (pintype "output"))
    )
    (net (code "42") (name "Net-(U10-A3)") (class "Default")
      (node (ref "U10") (pin "5") (pinfunction "A3_5") (pintype "input"))
      (node (ref "U11") (pin "6") (pinfunction "~{Y2}_6") (pintype "output"))
    )
    (net (code "43") (name "Net-(U10-A4)") (class "Default")
      (node (ref "U10") (pin "9") (pinfunction "A4_9") (pintype "input"))
      (node (ref "U11") (pin "14") (pinfunction "~{Y3}_14") (pintype "output"))
    )
    (net (code "44") (name "Net-(U10-Y1)") (class "Default")
      (node (ref "R8") (pin "2") (pinfunction "2_2") (pintype "passive"))
      (node (ref "U10") (pin "2") (pinfunction "Y1_2") (pintype "output"))
      (node (ref "U13") (pin "4") (pinfunction "S1_4") (pintype "input"))
      (node (ref "U8") (pin "4") (pinfunction "S1_4") (pintype "input"))
    )
    (net (code "45") (name "Net-(U10-Y2)") (class "Default")
      (node (ref "R12") (pin "2") (pinfunction "2_2") (pintype "passive"))
      (node (ref "U10") (pin "4") (pinfunction "Y2_4") (pintype "output"))
      (node (ref "U13") (pin "6") (pinfunction "S2_6") (pintype "input"))
      (node (ref "U8") (pin "6") (pinfunction "S2_6") (pintype "input"))
    )
    (net (code "46") (name "Net-(U10-Y3)") (class "Default")
      (node (ref "R13") (pin "2") (pinfunction "2_2") (pintype "passive"))
      (node (ref "U10") (pin "6") (pinfunction "Y3_6") (pintype "output"))
      (node (ref "U13") (pin "12") (pinfunction "S3_12") (pintype "input"))
      (node (ref "U8") (pin "12") (pinfunction "S3_12") (pintype "input"))
    )
    (net (code "47") (name "Net-(U10-Y4)") (class "Default")
      (node (ref "R14") (pin "2") (pinfunction "2_2") (pintype "passive"))
      (node (ref "U10") (pin "8") (pinfunction "Y4_8") (pintype "output"))
      (node (ref "U13") (pin "14") (pinfunction "S4_14") (pintype "input"))
      (node (ref "U8") (pin "14") (pinfunction "S4_14") (pintype "input"))
    )
    (net (code "48") (name "Net-(U10-Y5)") (class "Default")
      (node (ref "R1") (pin "1") (pinfunction "1_1") (pintype "passive"))
      (node (ref "U10") (pin "10") (pinfunction "Y5_10") (pintype "output"))
      (node (ref "U16") (pin "10") (pinfunction "RESET2_10") (pintype "input"))
      (node (ref "U16") (pin "4") (pinfunction "RESET1_4") (pintype "input"))
      (node (ref "U2") (pin "10") (pinfunction "RESET2_10") (pintype "input"))
      (node (ref "U2") (pin "4") (pinfunction "RESET1_4") (pintype "input"))
    )
    (net (code "49") (name "Net-(U11-~{I1})") (class "Default")
      (node (ref "R2") (pin "1") (pinfunction "1_1") (pintype "passive"))
      (node (ref "SW1") (pin "A") (pinfunction "A_A") (pintype "passive"))
      (node (ref "U11") (pin "11") (pinfunction "~{I1}_11") (pintype "input"))
    )
    (net (code "50") (name "Net-(U11-~{I2})") (class "Default")
      (node (ref "R3") (pin "1") (pinfunction "1_1") (pintype "passive"))
      (node (ref "SW2") (pin "A") (pinfunction "A_A") (pintype "passive"))
      (node (ref "U11") (pin "12") (pinfunction "~{I2}_12") (pintype "input"))
    )
    (net (code "51") (name "Net-(U11-~{I3})") (class "Default")
      (node (ref "R4") (pin "1") (pinfunction "1_1") (pintype "passive"))
      (node (ref "SW3") (pin "A") (pinfunction "A_A") (pintype "passive"))
      (node (ref "U11") (pin "13") (pinfunction "~{I3}_13") (pintype "input"))
    )
    (net (code "52") (name "Net-(U11-~{I4})") (class "Default")
      (node (ref "R7") (pin "1") (pinfunction "1_1") (pintype "passive"))
      (node (ref "SW4") (pin "A") (pinfunction "A_A") (pintype "passive"))
      (node (ref "U11") (pin "1") (pinfunction "~{I4}_1") (pintype "input"))
    )
    (net (code "53") (name "Net-(U11-~{I5})") (class "Default")
      (node (ref "R5") (pin "1") (pinfunction "1_1") (pintype "passive"))
      (node (ref "SW5") (pin "A") (pinfunction "A_A") (pintype "passive"))
      (node (ref "U11") (pin "2") (pinfunction "~{I5}_2") (pintype "input"))
    )
    (net (code "54") (name "Net-(U11-~{I6})") (class "Default")
      (node (ref "R6") (pin "1") (pinfunction "1_1") (pintype "passive"))
      (node (ref "SW6") (pin "A") (pinfunction "A_A") (pintype "passive"))
      (node (ref "U11") (pin "3") (pinfunction "~{I6}_3") (pintype "input"))
    )
    (net (code "55") (name "Net-(U11-~{I7})") (class "Default")
      (node (ref "R11") (pin "1") (pinfunction "1_1") (pintype "passive"))
      (node (ref "SW7") (pin "A") (pinfunction "A_A") (pintype "passive"))
      (node (ref "U11") (pin "4") (pinfunction "~{I7}_4") (pintype "input"))
    )
    (net (code "56") (name "Net-(U11-~{I8})") (class "Default")
      (node (ref "R9") (pin "1") (pinfunction "1_1") (pintype "passive"))
      (node (ref "SW8") (pin "A") (pinfunction "A_A") (pintype "passive"))
      (node (ref "U11") (pin "5") (pinfunction "~{I8}_5") (pintype "input"))
    )
    (net (code "57") (name "Net-(U11-~{I9})") (class "Default")
      (node (ref "R10") (pin "1") (pinfunction "1_1") (pintype "passive"))
      (node (ref "SW9") (pin "A") (pinfunction "A_A") (pintype "passive"))
      (node (ref "U11") (pin "10") (pinfunction "~{I9}_10") (pintype "input"))
    )
    (net (code "58") (name "Net-(U12-Q0)") (class "Default")
      (node (ref "U12") (pin "15") (pinfunction "Q0_15") (pintype "output"))
      (node (ref "U22") (pin "1") (pinfunction "A_1") (pintype "input"))
      (node (ref "U23") (pin "2") (pinfunction "A_2") (pintype "input"))
    )
    (net (code "59") (name "Net-(U12-Q1)") (class "Default")
      (node (ref "U12") (pin "14") (pinfunction "Q1_14") (pintype "output"))
      (node (ref "U22") (pin "5") (pinfunction "C_5") (pintype "input"))
      (node (ref "U23") (pin "3") (pinfunction "B_3") (pintype "input"))
    )
    (net (code "60") (name "Net-(U12-Q2)") (class "Default")
      (node (ref "U12") (pin "13") (pinfunction "Q2_13") (pintype "output"))
      (node (ref "U22") (pin "8") (pinfunction "E_8") (pintype "input"))
      (node (ref "U23") (pin "4") (pinfunction "C_4") (pintype "input"))
    )
    (net (code "61") (name "Net-(U12-Q3)") (class "Default")
      (node (ref "U12") (pin "12") (pinfunction "Q3_12") (pintype "output"))
      (node (ref "U22") (pin "12") (pinfunction "G_12") (pintype "input"))
      (node (ref "U23") (pin "5") (pinfunction "D_5") (pintype "input"))
    )
    (net (code "62") (name "Net-(U12-S0)") (class "Default")
      (node (ref "U12") (pin "10") (pinfunction "S1_10") (pintype "input"))
      (node (ref "U12") (pin "9") (pinfunction "S0_9") (pintype "input"))
      (node (ref "U5") (pin "7") (pinfunction "Q3_7") (pintype "output"))
    )
    (net (code "63") (name "Net-(U13-Q1)") (class "Default")
      (node (ref "U13") (pin "2") (pinfunction "Q1_2") (pintype "output"))
      (node (ref "U14") (pin "3") (pinfunction "D0_3") (pintype "input"))
      (node (ref "U15") (pin "3") (pinfunction "D0_3") (pintype "input"))
      (node (ref "U17") (pin "3") (pinfunction "D0_3") (pintype "input"))
      (node (ref "U18") (pin "3") (pinfunction "D0_3") (pintype "input"))
      (node (ref "U6") (pin "9") (pinfunction "E_9") (pintype "input"))
    )
    (net (code "64") (name "Net-(U13-Q2)") (class "Default")
      (node (ref "U13") (pin "9") (pinfunction "Q2_9") (pintype "output"))
      (node (ref "U14") (pin "4") (pinfunction "D1_4") (pintype "input"))
      (node (ref "U15") (pin "4") (pinfunction "D1_4") (pintype "input"))
      (node (ref "U17") (pin "4") (pinfunction "D1_4") (pintype "input"))
      (node (ref "U18") (pin "4") (pinfunction "D1_4") (pintype "input"))
      (node (ref "U6") (pin "10") (pinfunction "F_10") (pintype "input"))
    )
    (net (code "65") (name "Net-(U13-Q3)") (class "Default")
      (node (ref "U13") (pin "10") (pinfunction "Q3_10") (pintype "output"))
      (node (ref "U14") (pin "5") (pinfunction "D2_5") (pintype "input"))
      (node (ref "U15") (pin "5") (pinfunction "D2_5") (pintype "input"))
      (node (ref "U17") (pin "5") (pinfunction "D2_5") (pintype "input"))
      (node (ref "U18") (pin "5") (pinfunction "D2_5") (pintype "input"))
      (node (ref "U6") (pin "11") (pinfunction "G_11") (pintype "input"))
    )
    (net (code "66") (name "Net-(U13-Q4)") (class "Default")
      (node (ref "U13") (pin "1") (pinfunction "Q4_1") (pintype "output"))
      (node (ref "U14") (pin "6") (pinfunction "D3_6") (pintype "input"))
      (node (ref "U15") (pin "6") (pinfunction "D3_6") (pintype "input"))
      (node (ref "U17") (pin "6") (pinfunction "D3_6") (pintype "input"))
      (node (ref "U18") (pin "6") (pinfunction "D3_6") (pintype "input"))
      (node (ref "U6") (pin "12") (pinfunction "H_12") (pintype "input"))
    )
    (net (code "67") (name "Net-(U14-CP)") (class "Default")
      (node (ref "U14") (pin "11") (pinfunction "CP_11") (pintype "input"))
      (node (ref "U15") (pin "11") (pinfunction "CP_11") (pintype "input"))
      (node (ref "U17") (pin "11") (pinfunction "CP_11") (pintype "input"))
      (node (ref "U18") (pin "11") (pinfunction "CP_11") (pintype "input"))
      (node (ref "U9") (pin "12") (pinfunction "12_12") (pintype "passive"))
    )
    (net (code "68") (name "Net-(U14-Q0)") (class "Default")
      (node (ref "U14") (pin "15") (pinfunction "Q0_15") (pintype "output"))
      (node (ref "U19") (pin "2") (pinfunction "B_2") (pintype "input"))
    )
    (net (code "69") (name "Net-(U14-Q1)") (class "Default")
      (node (ref "U14") (pin "14") (pinfunction "Q1_14") (pintype "output"))
      (node (ref "U19") (pin "6") (pinfunction "D_6") (pintype "input"))
    )
    (net (code "70") (name "Net-(U14-Q2)") (class "Default")
      (node (ref "U14") (pin "13") (pinfunction "Q2_13") (pintype "output"))
      (node (ref "U19") (pin "9") (pinfunction "F_9") (pintype "input"))
    )
    (net (code "71") (name "Net-(U14-Q3)") (class "Default")
      (node (ref "U14") (pin "12") (pinfunction "Q3_12") (pintype "output"))
      (node (ref "U19") (pin "13") (pinfunction "H_13") (pintype "input"))
    )
    (net (code "72") (name "Net-(U14-S0)") (class "Default")
      (node (ref "U14") (pin "10") (pinfunction "S1_10") (pintype "input"))
      (node (ref "U14") (pin "9") (pinfunction "S0_9") (pintype "input"))
      (node (ref "U4") (pin "12") (pinfunction "Q0_12") (pintype "output"))
    )
    (net (code "73") (name "Net-(U15-Q0)") (class "Default")
      (node (ref "U15") (pin "15") (pinfunction "Q0_15") (pintype "output"))
      (node (ref "U20") (pin "2") (pinfunction "B_2") (pintype "input"))
    )
    (net (code "74") (name "Net-(U15-Q1)") (class "Default")
      (node (ref "U15") (pin "14") (pinfunction "Q1_14") (pintype "output"))
      (node (ref "U20") (pin "6") (pinfunction "D_6") (pintype "input"))
    )
    (net (code "75") (name "Net-(U15-Q2)") (class "Default")
      (node (ref "U15") (pin "13") (pinfunction "Q2_13") (pintype "output"))
      (node (ref "U20") (pin "9") (pinfunction "F_9") (pintype "input"))
    )
    (net (code "76") (name "Net-(U15-Q3)") (class "Default")
      (node (ref "U15") (pin "12") (pinfunction "Q3_12") (pintype "output"))
      (node (ref "U20") (pin "13") (pinfunction "H_13") (pintype "input"))
    )
    (net (code "77") (name "Net-(U15-S0)") (class "Default")
      (node (ref "U15") (pin "10") (pinfunction "S1_10") (pintype "input"))
      (node (ref "U15") (pin "9") (pinfunction "S0_9") (pintype "input"))
      (node (ref "U4") (pin "11") (pinfunction "Q1_11") (pintype "output"))
    )
    (net (code "78") (name "Net-(U16A-CLOCK1)") (class "Default")
      (node (ref "U16") (pin "12") (pinfunction "Q2_12") (pintype "output"))
      (node (ref "U16") (pin "3") (pinfunction "CLOCK1_3") (pintype "input"))
      (node (ref "U16") (pin "9") (pinfunction "D2_9") (pintype "input"))
    )
    (net (code "79") (name "Net-(U16A-D1)") (class "Default")
      (node (ref "U16") (pin "2") (pinfunction "Q1_2") (pintype "output"))
      (node (ref "U16") (pin "5") (pinfunction "D1_5") (pintype "input"))
    )
    (net (code "80") (name "Net-(U16B-CLOCK2)") (class "Default")
      (node (ref "U16") (pin "11") (pinfunction "CLOCK2_11") (pintype "input"))
      (node (ref "U6") (pin "13") (pinfunction "K_13") (pintype "output"))
      (node (ref "U9") (pin "13") (pinfunction "13_13") (pintype "passive"))
    )
    (net (code "81") (name "Net-(U17-Q0)") (class "Default")
      (node (ref "U17") (pin "15") (pinfunction "Q0_15") (pintype "output"))
      (node (ref "U21") (pin "2") (pinfunction "B_2") (pintype "input"))
    )
    (net (code "82") (name "Net-(U17-Q1)") (class "Default")
      (node (ref "U17") (pin "14") (pinfunction "Q1_14") (pintype "output"))
      (node (ref "U21") (pin "6") (pinfunction "D_6") (pintype "input"))
    )
    (net (code "83") (name "Net-(U17-Q2)") (class "Default")
      (node (ref "U17") (pin "13") (pinfunction "Q2_13") (pintype "output"))
      (node (ref "U21") (pin "9") (pinfunction "F_9") (pintype "input"))
    )
    (net (code "84") (name "Net-(U17-Q3)") (class "Default")
      (node (ref "U17") (pin "12") (pinfunction "Q3_12") (pintype "output"))
      (node (ref "U21") (pin "13") (pinfunction "H_13") (pintype "input"))
    )
    (net (code "85") (name "Net-(U17-S0)") (class "Default")
      (node (ref "U17") (pin "10") (pinfunction "S1_10") (pintype "input"))
      (node (ref "U17") (pin "9") (pinfunction "S0_9") (pintype "input"))
      (node (ref "U4") (pin "10") (pinfunction "Q2_10") (pintype "output"))
    )
    (net (code "86") (name "Net-(U18-Q0)") (class "Default")
      (node (ref "U18") (pin "15") (pinfunction "Q0_15") (pintype "output"))
      (node (ref "U22") (pin "2") (pinfunction "B_2") (pintype "input"))
    )
    (net (code "87") (name "Net-(U18-Q1)") (class "Default")
      (node (ref "U18") (pin "14") (pinfunction "Q1_14") (pintype "output"))
      (node (ref "U22") (pin "6") (pinfunction "D_6") (pintype "input"))
    )
    (net (code "88") (name "Net-(U18-Q2)") (class "Default")
      (node (ref "U18") (pin "13") (pinfunction "Q2_13") (pintype "output"))
      (node (ref "U22") (pin "9") (pinfunction "F_9") (pintype "input"))
    )
    (net (code "89") (name "Net-(U18-Q3)") (class "Default")
      (node (ref "U18") (pin "12") (pinfunction "Q3_12") (pintype "output"))
      (node (ref "U22") (pin "13") (pinfunction "H_13") (pintype "input"))
    )
    (net (code "90") (name "Net-(U18-S0)") (class "Default")
      (node (ref "U18") (pin "10") (pinfunction "S1_10") (pintype "input"))
      (node (ref "U18") (pin "9") (pinfunction "S0_9") (pintype "input"))
      (node (ref "U4") (pin "9") (pinfunction "Q3_9") (pintype "output"))
    )
    (net (code "91") (name "Net-(U19A-J)") (class "Default")
      (node (ref "U19") (pin "3") (pinfunction "J_3") (pintype "output"))
      (node (ref "X1") (pin "1") (pinfunction "1A_1") (pintype "input"))
    )
    (net (code "92") (name "Net-(U19B-K)") (class "Default")
      (node (ref "U19") (pin "4") (pinfunction "K_4") (pintype "output"))
      (node (ref "X1") (pin "2") (pinfunction "1B_2") (pintype "input"))
    )
    (net (code "93") (name "Net-(U19C-L)") (class "Default")
      (node (ref "U19") (pin "10") (pinfunction "L_10") (pintype "output"))
      (node (ref "X1") (pin "4") (pinfunction "1C_4") (pintype "input"))
    )
    (net (code "94") (name "Net-(U19D-M)") (class "Default")
      (node (ref "U19") (pin "11") (pinfunction "M_11") (pintype "output"))
      (node (ref "X1") (pin "5") (pinfunction "1D_5") (pintype "input"))
    )
    (net (code "95") (name "Net-(U20A-A)") (class "Default")
      (node (ref "U20") (pin "1") (pinfunction "A_1") (pintype "input"))
      (node (ref "U3") (pin "15") (pinfunction "Q0_15") (pintype "output"))
    )
    (net (code "96") (name "Net-(U20A-J)") (class "Default")
      (node (ref "U20") (pin "3") (pinfunction "J_3") (pintype "output"))
      (node (ref "X1") (pin "13") (pinfunction "2D_13") (pintype "input"))
    )
    (net (code "97") (name "Net-(U20B-C)") (class "Default")
      (node (ref "U20") (pin "5") (pinfunction "C_5") (pintype "input"))
      (node (ref "U3") (pin "14") (pinfunction "Q1_14") (pintype "output"))
    )
    (net (code "98") (name "Net-(U20B-K)") (class "Default")
      (node (ref "U20") (pin "4") (pinfunction "K_4") (pintype "output"))
      (node (ref "X1") (pin "12") (pinfunction "2C_12") (pintype "input"))
    )
    (net (code "99") (name "Net-(U20C-E)") (class "Default")
      (node (ref "U20") (pin "8") (pinfunction "E_8") (pintype "input"))
      (node (ref "U3") (pin "13") (pinfunction "Q2_13") (pintype "output"))
    )
    (net (code "100") (name "Net-(U20C-L)") (class "Default")
      (node (ref "U20") (pin "10") (pinfunction "L_10") (pintype "output"))
      (node (ref "X1") (pin "10") (pinfunction "2B_10") (pintype "input"))
    )
    (net (code "101") (name "Net-(U20D-G)") (class "Default")
      (node (ref "U20") (pin "12") (pinfunction "G_12") (pintype "input"))
      (node (ref "U3") (pin "12") (pinfunction "Q3_12") (pintype "output"))
    )
    (net (code "102") (name "Net-(U20D-M)") (class "Default")
      (node (ref "U20") (pin "11") (pinfunction "M_11") (pintype "output"))
      (node (ref "X1") (pin "9") (pinfunction "2A_9") (pintype "input"))
    )
    (net (code "103") (name "Net-(U21A-A)") (class "Default")
      (node (ref "U21") (pin "1") (pinfunction "A_1") (pintype "input"))
      (node (ref "U7") (pin "15") (pinfunction "Q0_15") (pintype "output"))
    )
    (net (code "104") (name "Net-(U21A-J)") (class "Default")
      (node (ref "U21") (pin "3") (pinfunction "J_3") (pintype "output"))
      (node (ref "X3") (pin "1") (pinfunction "1A_1") (pintype "input"))
    )
    (net (code "105") (name "Net-(U21B-C)") (class "Default")
      (node (ref "U21") (pin "5") (pinfunction "C_5") (pintype "input"))
      (node (ref "U7") (pin "14") (pinfunction "Q1_14") (pintype "output"))
    )
    (net (code "106") (name "Net-(U21B-K)") (class "Default")
      (node (ref "U21") (pin "4") (pinfunction "K_4") (pintype "output"))
      (node (ref "X3") (pin "2") (pinfunction "1B_2") (pintype "input"))
    )
    (net (code "107") (name "Net-(U21C-E)") (class "Default")
      (node (ref "U21") (pin "8") (pinfunction "E_8") (pintype "input"))
      (node (ref "U7") (pin "13") (pinfunction "Q2_13") (pintype "output"))
    )
    (net (code "108") (name "Net-(U21C-L)") (class "Default")
      (node (ref "U21") (pin "10") (pinfunction "L_10") (pintype "output"))
      (node (ref "X3") (pin "4") (pinfunction "1C_4") (pintype "input"))
    )
    (net (code "109") (name "Net-(U21D-G)") (class "Default")
      (node (ref "U21") (pin "12") (pinfunction "G_12") (pintype "input"))
      (node (ref "U7") (pin "12") (pinfunction "Q3_12") (pintype "output"))
    )
    (net (code "110") (name "Net-(U21D-M)") (class "Default")
      (node (ref "U21") (pin "11") (pinfunction "M_11") (pintype "output"))
      (node (ref "X3") (pin "5") (pinfunction "1D_5") (pintype "input"))
    )
    (net (code "111") (name "Net-(U22A-J)") (class "Default")
      (node (ref "U22") (pin "3") (pinfunction "J_3") (pintype "output"))
      (node (ref "X3") (pin "9") (pinfunction "2A_9") (pintype "input"))
    )
    (net (code "112") (name "Net-(U22B-K)") (class "Default")
      (node (ref "U22") (pin "4") (pinfunction "K_4") (pintype "output"))
      (node (ref "X3") (pin "10") (pinfunction "2B_10") (pintype "input"))
    )
    (net (code "113") (name "Net-(U22C-L)") (class "Default")
      (node (ref "U22") (pin "10") (pinfunction "L_10") (pintype "output"))
      (node (ref "X3") (pin "12") (pinfunction "2C_12") (pintype "input"))
    )
    (net (code "114") (name "Net-(U22D-M)") (class "Default")
      (node (ref "U22") (pin "11") (pinfunction "M_11") (pintype "output"))
      (node (ref "X3") (pin "13") (pinfunction "2D_13") (pintype "input"))
    )
    (net (code "115") (name "Net-(U23A-J)") (class "Default")
      (node (ref "U23") (pin "1") (pinfunction "J_1") (pintype "output"))
      (node (ref "U5") (pin "15") (pinfunction "~{E}_15") (pintype "input"))
    )
    (net (code "116") (name "Net-(X1-1Y)") (class "Default")
      (node (ref "R17") (pin "2") (pinfunction "2_2") (pintype "passive"))
      (node (ref "X1") (pin "6") (pinfunction "1Y_6") (pintype "output"))
      (node (ref "X2") (pin "1") (pinfunction "1A_1") (pintype "input"))
    )
    (net (code "117") (name "Net-(X1-2Y)") (class "Default")
      (node (ref "R18") (pin "2") (pinfunction "2_2") (pintype "passive"))
      (node (ref "X1") (pin "8") (pinfunction "2Y_8") (pintype "output"))
      (node (ref "X2") (pin "2") (pinfunction "1B_2") (pintype "input"))
    )
    (net (code "118") (name "Net-(X2-1C)") (class "Default")
      (node (ref "R19") (pin "2") (pinfunction "2_2") (pintype "passive"))
      (node (ref "X2") (pin "4") (pinfunction "1C_4") (pintype "input"))
      (node (ref "X3") (pin "6") (pinfunction "1Y_6") (pintype "output"))
    )
    (net (code "119") (name "Net-(X2-1D)") (class "Default")
      (node (ref "R20") (pin "2") (pinfunction "2_2") (pintype "passive"))
      (node (ref "X2") (pin "5") (pinfunction "1D_5") (pintype "input"))
      (node (ref "X3") (pin "8") (pinfunction "2Y_8") (pintype "output"))
    )
    (net (code "120") (name "unconnected-(SW1-PadA')") (class "Default")
      (node (ref "SW1") (pin "A'") (pinfunction "A'_A'") (pintype "passive"))
    )
    (net (code "121") (name "unconnected-(SW1-PadB)") (class "Default")
      (node (ref "SW1") (pin "B") (pinfunction "B_B") (pintype "passive"))
    )
    (net (code "122") (name "unconnected-(SW2-PadA')") (class "Default")
      (node (ref "SW2") (pin "A'") (pinfunction "A'_A'") (pintype "passive"))
    )
    (net (code "123") (name "unconnected-(SW2-PadB)") (class "Default")
      (node (ref "SW2") (pin "B") (pinfunction "B_B") (pintype "passive"))
    )
    (net (code "124") (name "unconnected-(SW3-PadA')") (class "Default")
      (node (ref "SW3") (pin "A'") (pinfunction "A'_A'") (pintype "passive"))
    )
    (net (code "125") (name "unconnected-(SW3-PadB)") (class "Default")
      (node (ref "SW3") (pin "B") (pinfunction "B_B") (pintype "passive"))
    )
    (net (code "126") (name "unconnected-(SW4-PadA')") (class "Default")
      (node (ref "SW4") (pin "A'") (pinfunction "A'_A'") (pintype "passive"))
    )
    (net (code "127") (name "unconnected-(SW4-PadB)") (class "Default")
      (node (ref "SW4") (pin "B") (pinfunction "B_B") (pintype "passive"))
    )
    (net (code "128") (name "unconnected-(SW5-PadA')") (class "Default")
      (node (ref "SW5") (pin "A'") (pinfunction "A'_A'") (pintype "passive"))
    )
    (net (code "129") (name "unconnected-(SW5-PadB)") (class "Default")
      (node (ref "SW5") (pin "B") (pinfunction "B_B") (pintype "passive"))
    )
    (net (code "130") (name "unconnected-(SW6-PadA')") (class "Default")
      (node (ref "SW6") (pin "A'") (pinfunction "A'_A'") (pintype "passive"))
    )
    (net (code "131") (name "unconnected-(SW6-PadB)") (class "Default")
      (node (ref "SW6") (pin "B") (pinfunction "B_B") (pintype "passive"))
    )
    (net (code "132") (name "unconnected-(SW7-PadA')") (class "Default")
      (node (ref "SW7") (pin "A'") (pinfunction "A'_A'") (pintype "passive"))
    )
    (net (code "133") (name "unconnected-(SW7-PadB)") (class "Default")
      (node (ref "SW7") (pin "B") (pinfunction "B_B") (pintype "passive"))
    )
    (net (code "134") (name "unconnected-(SW8-PadA')") (class "Default")
      (node (ref "SW8") (pin "A'") (pinfunction "A'_A'") (pintype "passive"))
    )
    (net (code "135") (name "unconnected-(SW8-PadB)") (class "Default")
      (node (ref "SW8") (pin "B") (pinfunction "B_B") (pintype "passive"))
    )
    (net (code "136") (name "unconnected-(SW9-PadA')") (class "Default")
      (node (ref "SW9") (pin "A'") (pinfunction "A'_A'") (pintype "passive"))
    )
    (net (code "137") (name "unconnected-(SW9-PadB)") (class "Default")
      (node (ref "SW9") (pin "B") (pinfunction "B_B") (pintype "passive"))
    )
    (net (code "138") (name "unconnected-(U1-DSL-Pad7)") (class "Default")
      (node (ref "U1") (pin "7") (pinfunction "DSL_7") (pintype "input+no_connect"))
    )
    (net (code "139") (name "unconnected-(U1-DSR-Pad2)") (class "Default")
      (node (ref "U1") (pin "2") (pinfunction "DSR_2") (pintype "input+no_connect"))
    )
    (net (code "140") (name "unconnected-(U3-DSL-Pad7)") (class "Default")
      (node (ref "U3") (pin "7") (pinfunction "DSL_7") (pintype "input+no_connect"))
    )
    (net (code "141") (name "unconnected-(U3-DSR-Pad2)") (class "Default")
      (node (ref "U3") (pin "2") (pinfunction "DSR_2") (pintype "input+no_connect"))
    )
    (net (code "142") (name "unconnected-(U4A-Q2-Pad6)") (class "Default")
      (node (ref "U4") (pin "6") (pinfunction "Q2_6") (pintype "output+no_connect"))
    )
    (net (code "143") (name "unconnected-(U4A-Q3-Pad7)") (class "Default")
      (node (ref "U4") (pin "7") (pinfunction "Q3_7") (pintype "output+no_connect"))
    )
    (net (code "144") (name "unconnected-(U5B-B-Pad13)") (class "Default")
      (node (ref "U5") (pin "13") (pinfunction "B_13") (pintype "input+no_connect"))
    )
    (net (code "145") (name "unconnected-(U5B-Q2-Pad10)") (class "Default")
      (node (ref "U5") (pin "10") (pinfunction "Q2_10") (pintype "output+no_connect"))
    )
    (net (code "146") (name "unconnected-(U5B-Q3-Pad9)") (class "Default")
      (node (ref "U5") (pin "9") (pinfunction "Q3_9") (pintype "output+no_connect"))
    )
    (net (code "147") (name "unconnected-(U6C-NC-Pad6)") (class "Default")
      (node (ref "U6") (pin "6") (pinfunction "NC_6") (pintype "passive+no_connect"))
    )
    (net (code "148") (name "unconnected-(U6C-NC-Pad8)") (class "Default")
      (node (ref "U6") (pin "8") (pinfunction "NC_8") (pintype "passive+no_connect"))
    )
    (net (code "149") (name "unconnected-(U7-DSL-Pad7)") (class "Default")
      (node (ref "U7") (pin "7") (pinfunction "DSL_7") (pintype "input+no_connect"))
    )
    (net (code "150") (name "unconnected-(U7-DSR-Pad2)") (class "Default")
      (node (ref "U7") (pin "2") (pinfunction "DSR_2") (pintype "input+no_connect"))
    )
    (net (code "151") (name "unconnected-(U9-Pad3)") (class "Default")
      (node (ref "U9") (pin "3") (pinfunction "3_3") (pintype "passive+no_connect"))
    )
    (net (code "152") (name "unconnected-(U9-Pad4)") (class "Default")
      (node (ref "U9") (pin "4") (pinfunction "4_4") (pintype "passive+no_connect"))
    )
    (net (code "153") (name "unconnected-(U9-Pad5)") (class "Default")
      (node (ref "U9") (pin "5") (pinfunction "5_5") (pintype "passive+no_connect"))
    )
    (net (code "154") (name "unconnected-(U9-Pad6)") (class "Default")
      (node (ref "U9") (pin "6") (pinfunction "6_6") (pintype "passive+no_connect"))
    )
    (net (code "155") (name "unconnected-(U9-Pad8)") (class "Default")
      (node (ref "U9") (pin "8") (pinfunction "8_8") (pintype "passive+no_connect"))
    )
    (net (code "156") (name "unconnected-(U9-Pad9)") (class "Default")
      (node (ref "U9") (pin "9") (pinfunction "9_9") (pintype "passive+no_connect"))
    )
    (net (code "157") (name "unconnected-(U9-Pad10)") (class "Default")
      (node (ref "U9") (pin "10") (pinfunction "10_10") (pintype "passive+no_connect"))
    )
    (net (code "158") (name "unconnected-(U9-Pad11)") (class "Default")
      (node (ref "U9") (pin "11") (pinfunction "11_11") (pintype "passive+no_connect"))
    )
    (net (code "159") (name "unconnected-(U10-A6-Pad13)") (class "Default")
      (node (ref "U10") (pin "13") (pinfunction "A6_13") (pintype "input+no_connect"))
    )
    (net (code "160") (name "unconnected-(U10-Y6-Pad12)") (class "Default")
      (node (ref "U10") (pin "12") (pinfunction "Y6_12") (pintype "output+no_connect"))
    )
    (net (code "161") (name "unconnected-(U11-NC-Pad15)") (class "Default")
      (node (ref "U11") (pin "15") (pinfunction "NC_15") (pintype "passive+no_connect"))
    )
    (net (code "162") (name "unconnected-(U12-DSL-Pad7)") (class "Default")
      (node (ref "U12") (pin "7") (pinfunction "DSL_7") (pintype "input+no_connect"))
    )
    (net (code "163") (name "unconnected-(U12-DSR-Pad2)") (class "Default")
      (node (ref "U12") (pin "2") (pinfunction "DSR_2") (pintype "input+no_connect"))
    )
    (net (code "164") (name "unconnected-(U14-DSL-Pad7)") (class "Default")
      (node (ref "U14") (pin "7") (pinfunction "DSL_7") (pintype "input+no_connect"))
    )
    (net (code "165") (name "unconnected-(U14-DSR-Pad2)") (class "Default")
      (node (ref "U14") (pin "2") (pinfunction "DSR_2") (pintype "input+no_connect"))
    )
    (net (code "166") (name "unconnected-(U14-~{MR}-Pad1)") (class "Default")
      (node (ref "U14") (pin "1") (pinfunction "~{MR}_1") (pintype "input+no_connect"))
    )
    (net (code "167") (name "unconnected-(U15-DSL-Pad7)") (class "Default")
      (node (ref "U15") (pin "7") (pinfunction "DSL_7") (pintype "input+no_connect"))
    )
    (net (code "168") (name "unconnected-(U15-DSR-Pad2)") (class "Default")
      (node (ref "U15") (pin "2") (pinfunction "DSR_2") (pintype "input+no_connect"))
    )
    (net (code "169") (name "unconnected-(U15-~{MR}-Pad1)") (class "Default")
      (node (ref "U15") (pin "1") (pinfunction "~{MR}_1") (pintype "input+no_connect"))
    )
    (net (code "170") (name "unconnected-(U17-DSL-Pad7)") (class "Default")
      (node (ref "U17") (pin "7") (pinfunction "DSL_7") (pintype "input+no_connect"))
    )
    (net (code "171") (name "unconnected-(U17-DSR-Pad2)") (class "Default")
      (node (ref "U17") (pin "2") (pinfunction "DSR_2") (pintype "input+no_connect"))
    )
    (net (code "172") (name "unconnected-(U17-~{MR}-Pad1)") (class "Default")
      (node (ref "U17") (pin "1") (pinfunction "~{MR}_1") (pintype "input+no_connect"))
    )
    (net (code "173") (name "unconnected-(U18-DSL-Pad7)") (class "Default")
      (node (ref "U18") (pin "7") (pinfunction "DSL_7") (pintype "input+no_connect"))
    )
    (net (code "174") (name "unconnected-(U18-DSR-Pad2)") (class "Default")
      (node (ref "U18") (pin "2") (pinfunction "DSR_2") (pintype "input+no_connect"))
    )
    (net (code "175") (name "unconnected-(U18-~{MR}-Pad1)") (class "Default")
      (node (ref "U18") (pin "1") (pinfunction "~{MR}_1") (pintype "input+no_connect"))
    )
    (net (code "176") (name "unconnected-(U23B-E-Pad9)") (class "Default")
      (node (ref "U23") (pin "9") (pinfunction "E_9") (pintype "input+no_connect"))
    )
    (net (code "177") (name "unconnected-(U23B-F-Pad10)") (class "Default")
      (node (ref "U23") (pin "10") (pinfunction "F_10") (pintype "input+no_connect"))
    )
    (net (code "178") (name "unconnected-(U23B-G-Pad11)") (class "Default")
      (node (ref "U23") (pin "11") (pinfunction "G_11") (pintype "input+no_connect"))
    )
    (net (code "179") (name "unconnected-(U23B-H-Pad12)") (class "Default")
      (node (ref "U23") (pin "12") (pinfunction "H_12") (pintype "input+no_connect"))
    )
    (net (code "180") (name "unconnected-(U23B-K-Pad13)") (class "Default")
      (node (ref "U23") (pin "13") (pinfunction "K_13") (pintype "output+no_connect"))
    )
    (net (code "181") (name "unconnected-(U23C-NC-Pad6)") (class "Default")
      (node (ref "U23") (pin "6") (pinfunction "NC_6") (pintype "passive+no_connect"))
    )
    (net (code "182") (name "unconnected-(U23C-NC-Pad8)") (class "Default")
      (node (ref "U23") (pin "8") (pinfunction "NC_8") (pintype "passive+no_connect"))
    )
    (net (code "183") (name "unconnected-(X1-Pad3)") (class "Default")
      (node (ref "X1") (pin "3") (pinfunction "3_3") (pintype "passive+no_connect"))
    )
    (net (code "184") (name "unconnected-(X1-Pad11)") (class "Default")
      (node (ref "X1") (pin "11") (pinfunction "11_11") (pintype "passive+no_connect"))
    )
    (net (code "185") (name "unconnected-(X2-2A-Pad9)") (class "Default")
      (node (ref "X2") (pin "9") (pinfunction "2A_9") (pintype "input+no_connect"))
    )
    (net (code "186") (name "unconnected-(X2-2B-Pad10)") (class "Default")
      (node (ref "X2") (pin "10") (pinfunction "2B_10") (pintype "input+no_connect"))
    )
    (net (code "187") (name "unconnected-(X2-2C-Pad12)") (class "Default")
      (node (ref "X2") (pin "12") (pinfunction "2C_12") (pintype "input+no_connect"))
    )
    (net (code "188") (name "unconnected-(X2-2D-Pad13)") (class "Default")
      (node (ref "X2") (pin "13") (pinfunction "2D_13") (pintype "input+no_connect"))
    )
    (net (code "189") (name "unconnected-(X2-2Y-Pad8)") (class "Default")
      (node (ref "X2") (pin "8") (pinfunction "2Y_8") (pintype "output+no_connect"))
    )
    (net (code "190") (name "unconnected-(X2-Pad3)") (class "Default")
      (node (ref "X2") (pin "3") (pinfunction "3_3") (pintype "passive+no_connect"))
    )
    (net (code "191") (name "unconnected-(X2-Pad11)") (class "Default")
      (node (ref "X2") (pin "11") (pinfunction "11_11") (pintype "passive+no_connect"))
    )
    (net (code "192") (name "unconnected-(X3-Pad3)") (class "Default")
      (node (ref "X3") (pin "3") (pinfunction "3_3") (pintype "passive+no_connect"))
    )
    (net (code "193") (name "unconnected-(X3-Pad11)") (class "Default")
      (node (ref "X3") (pin "11") (pinfunction "11_11") (pintype "passive+no_connect"))
    )
  )
)
